# EEZ_DIB_DCP405_r2B11.net
KiCad netlist of a schematic drawn in EAGLE
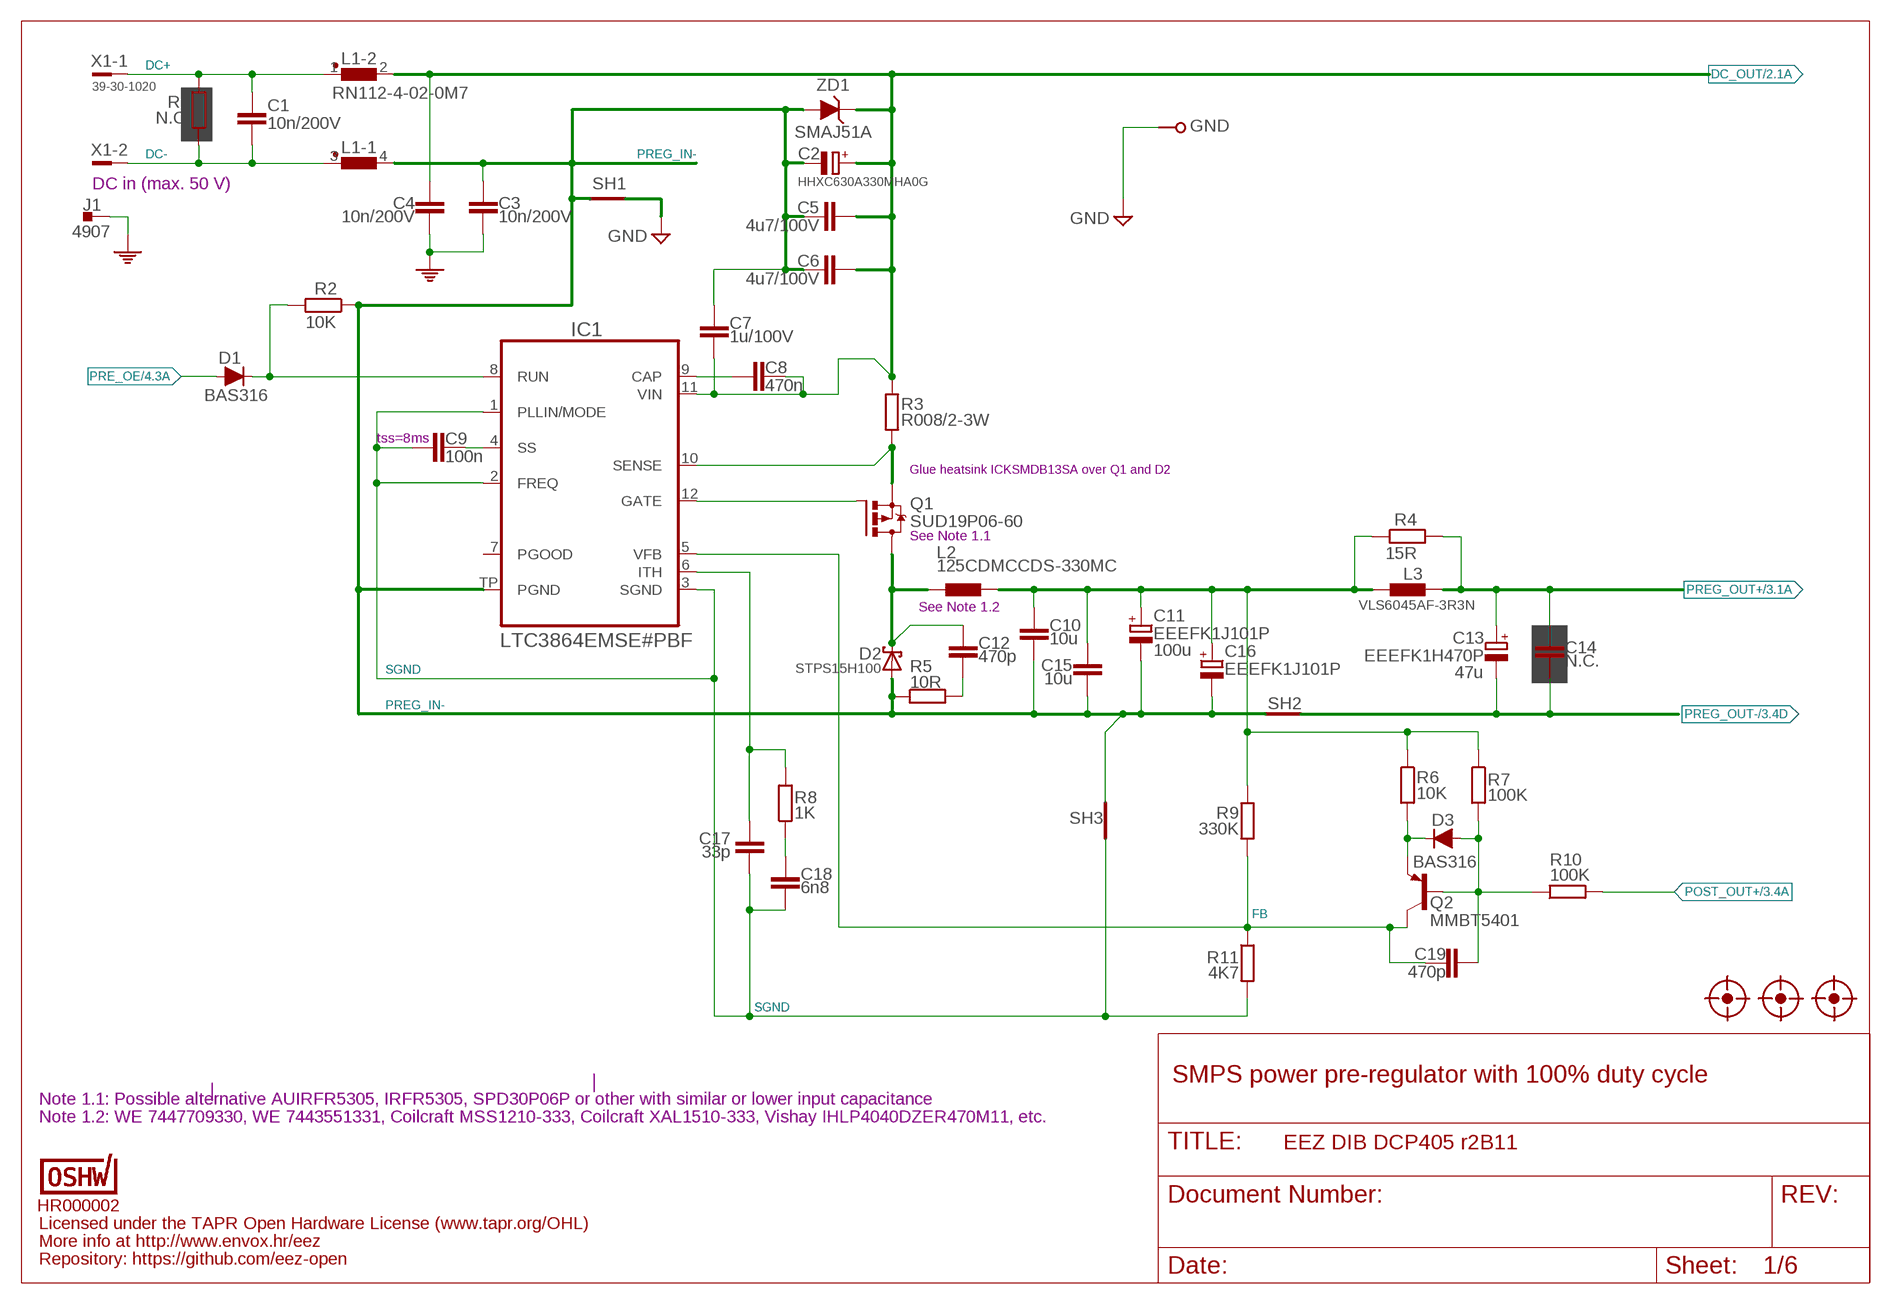
[diagram p0: schematic, sheet 1]
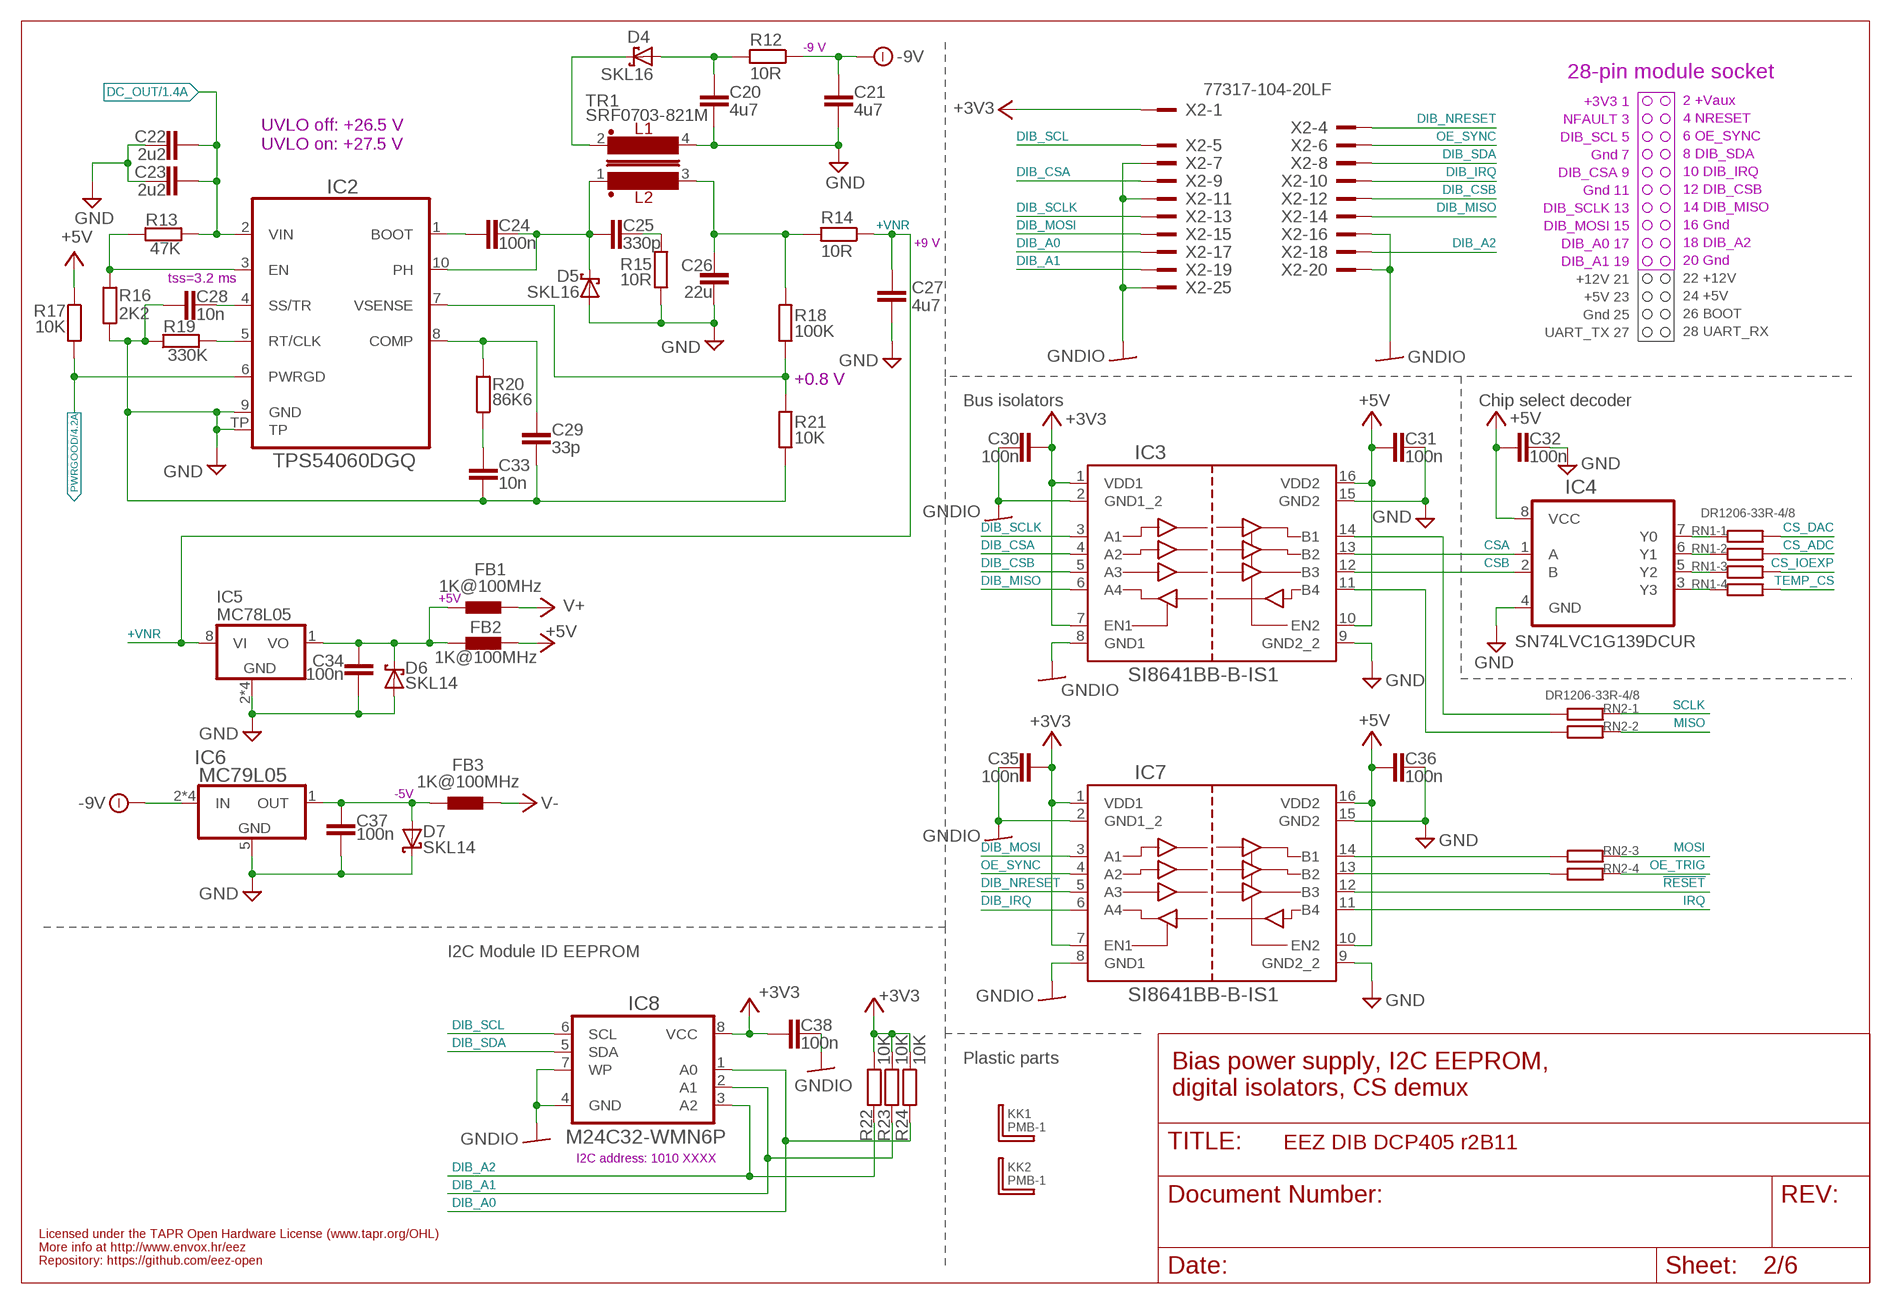
[diagram p1: schematic, sheet 2]
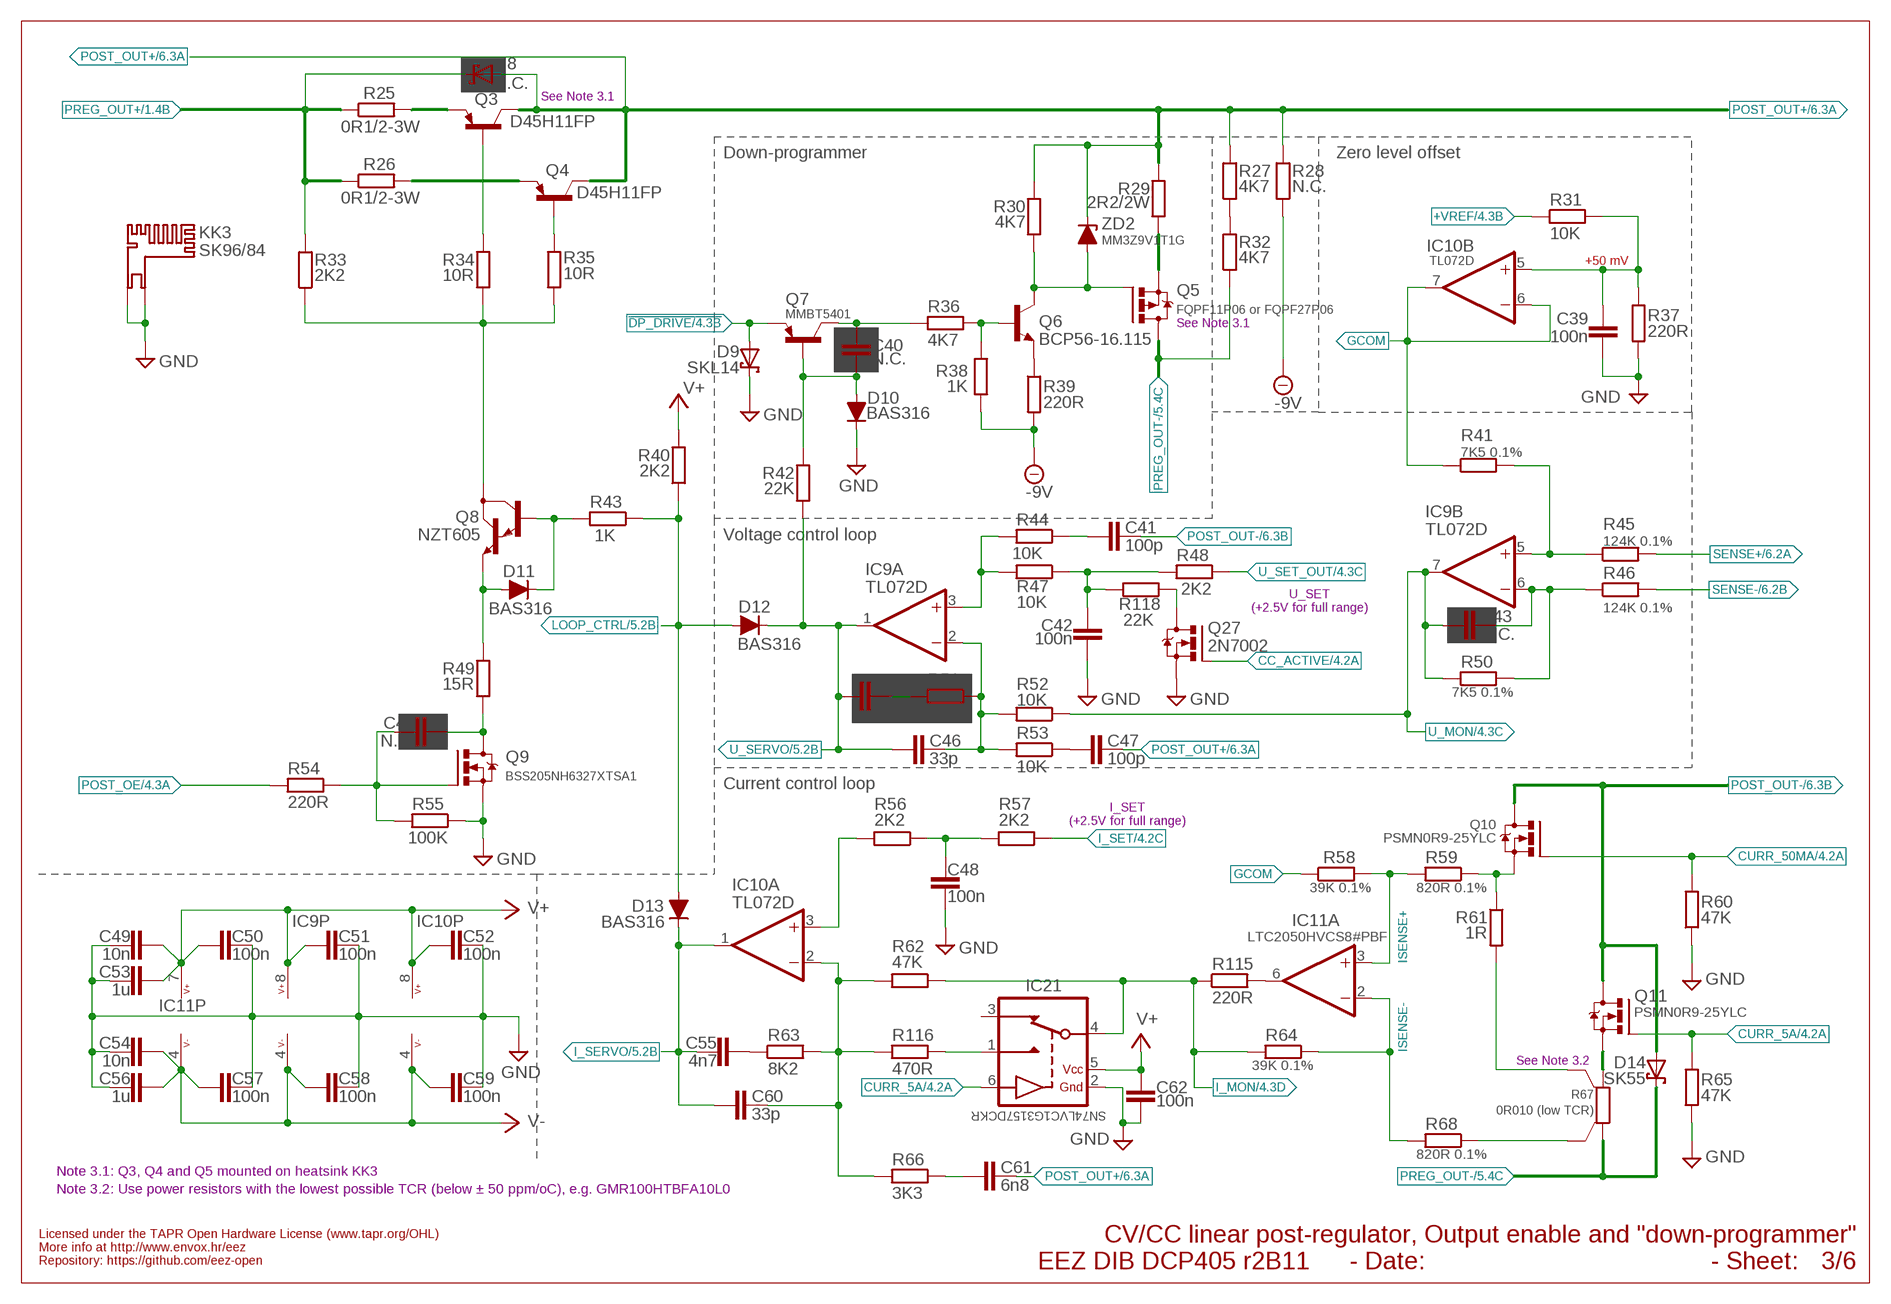
[diagram p2: schematic, sheet 3]
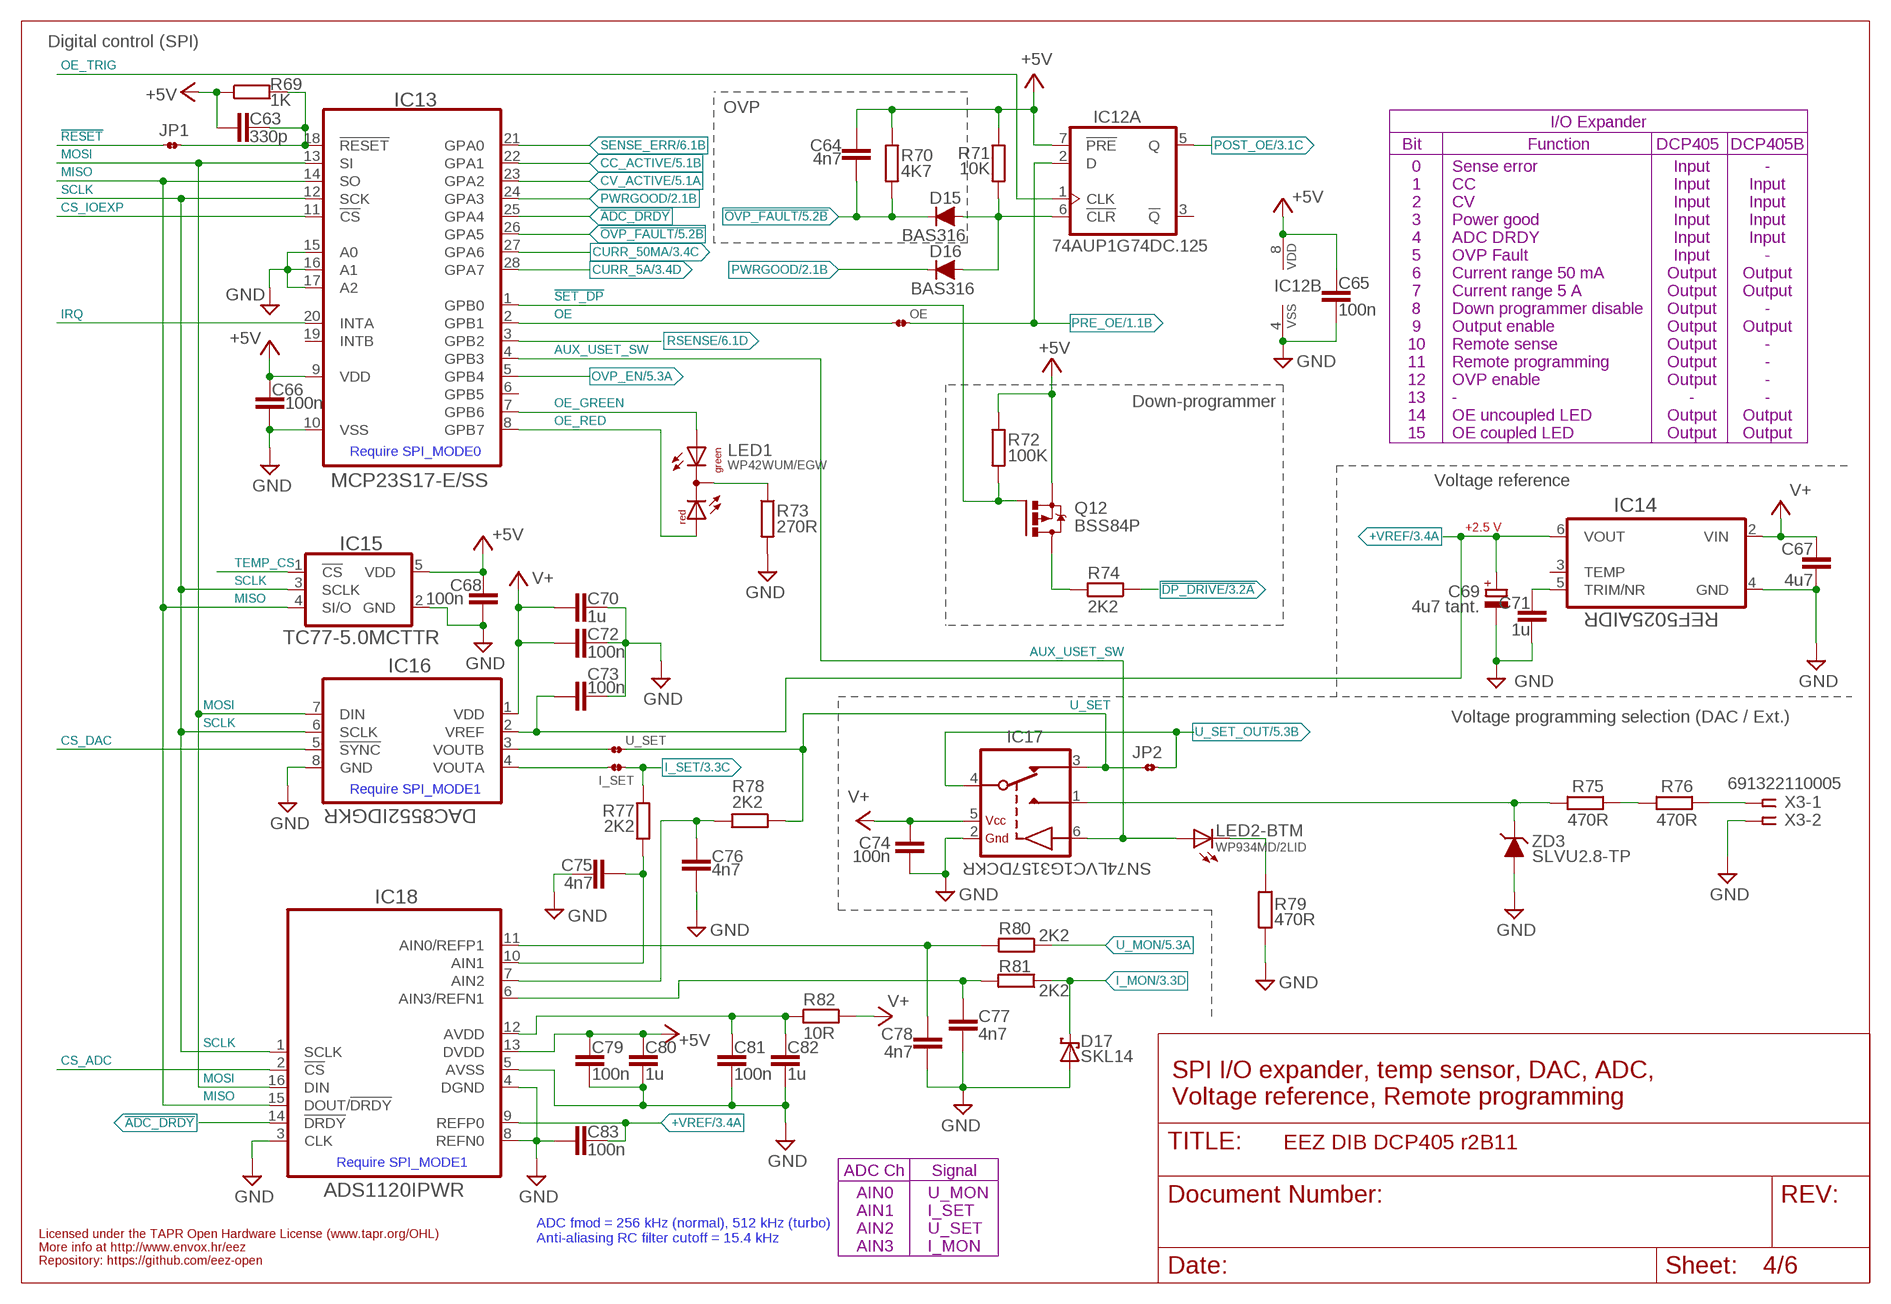
[diagram p3: schematic, sheet 4]
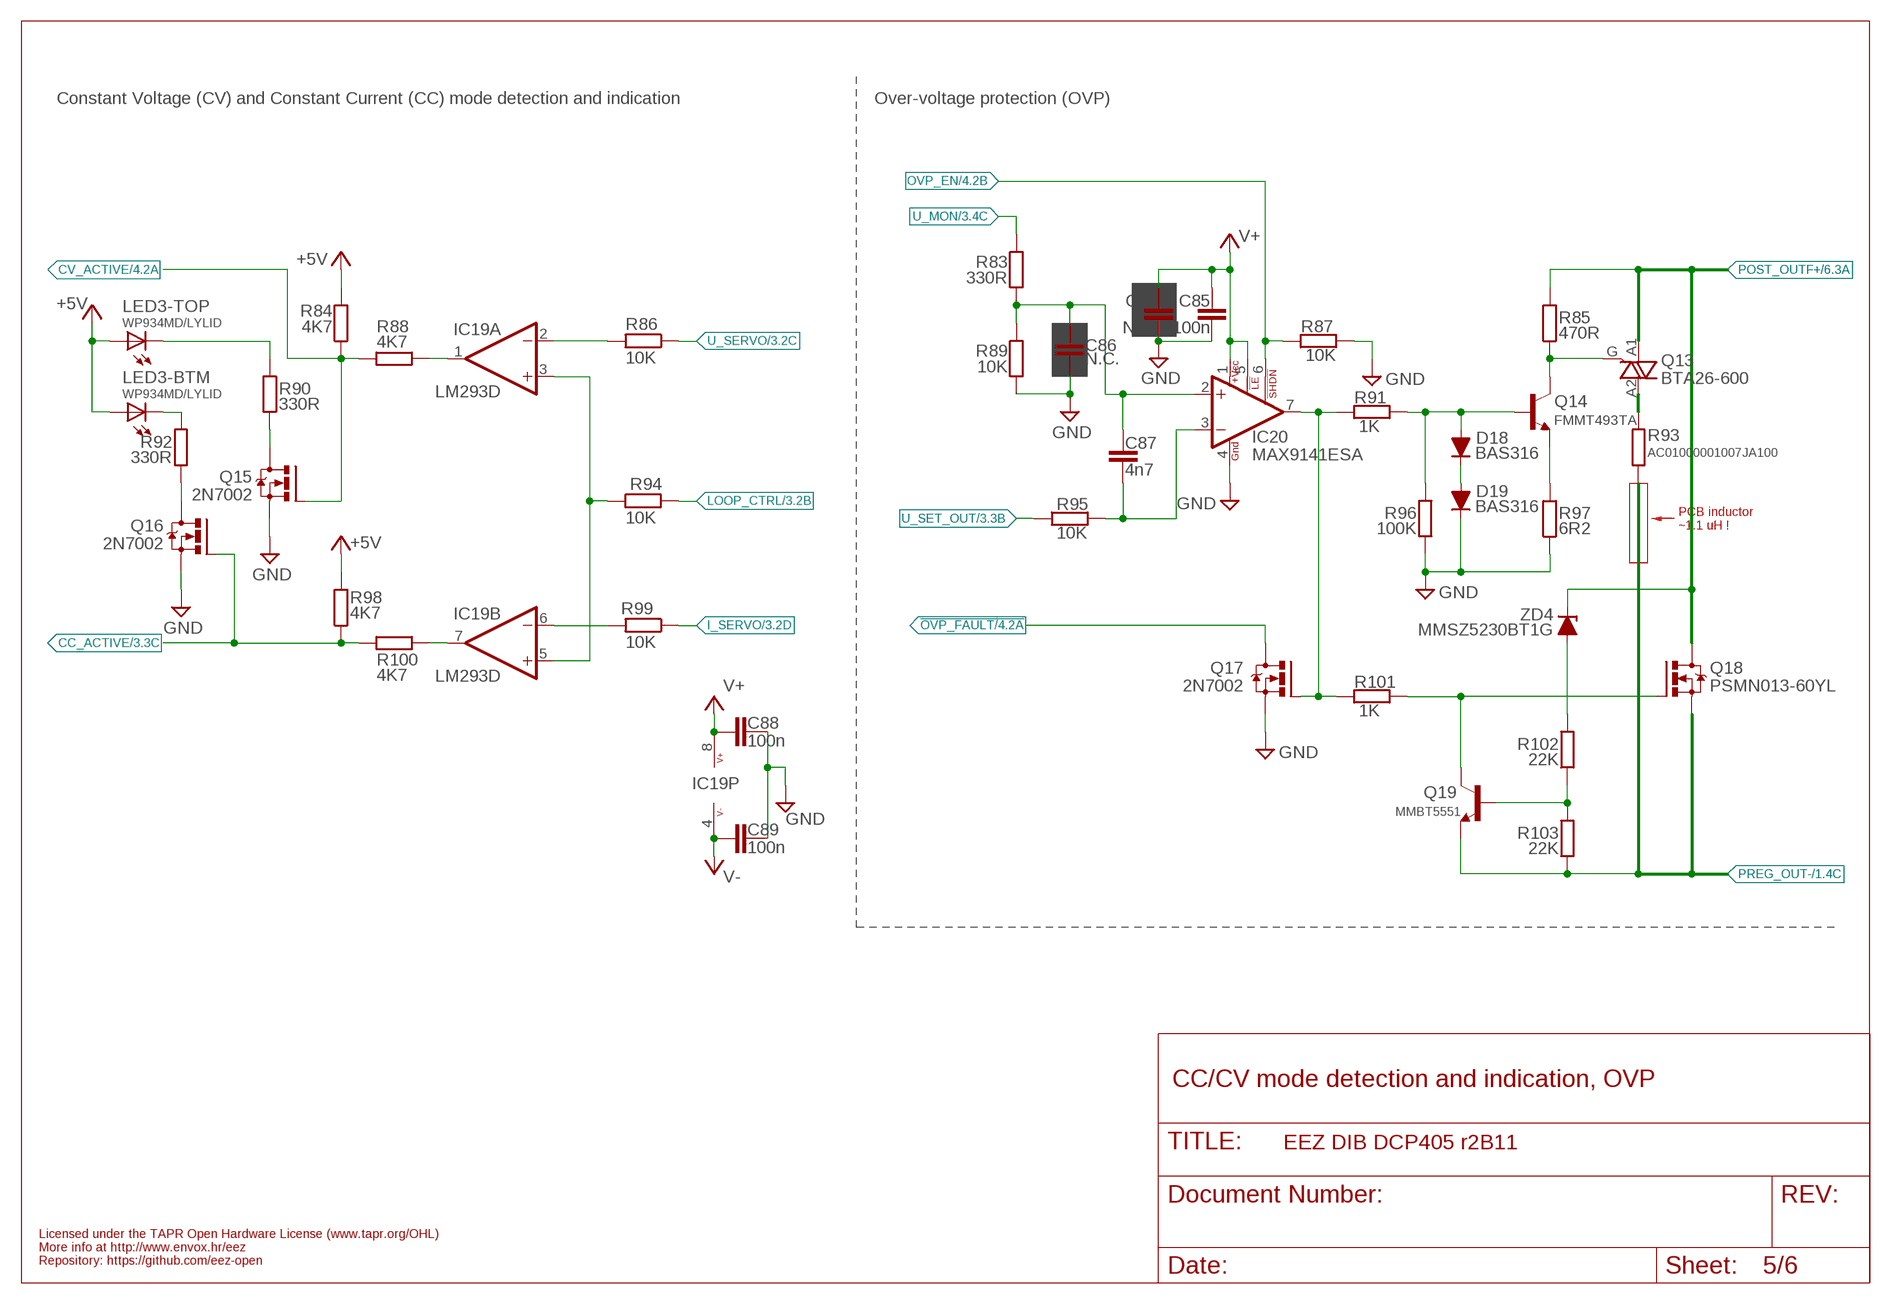
[diagram p4: schematic, sheet 5]
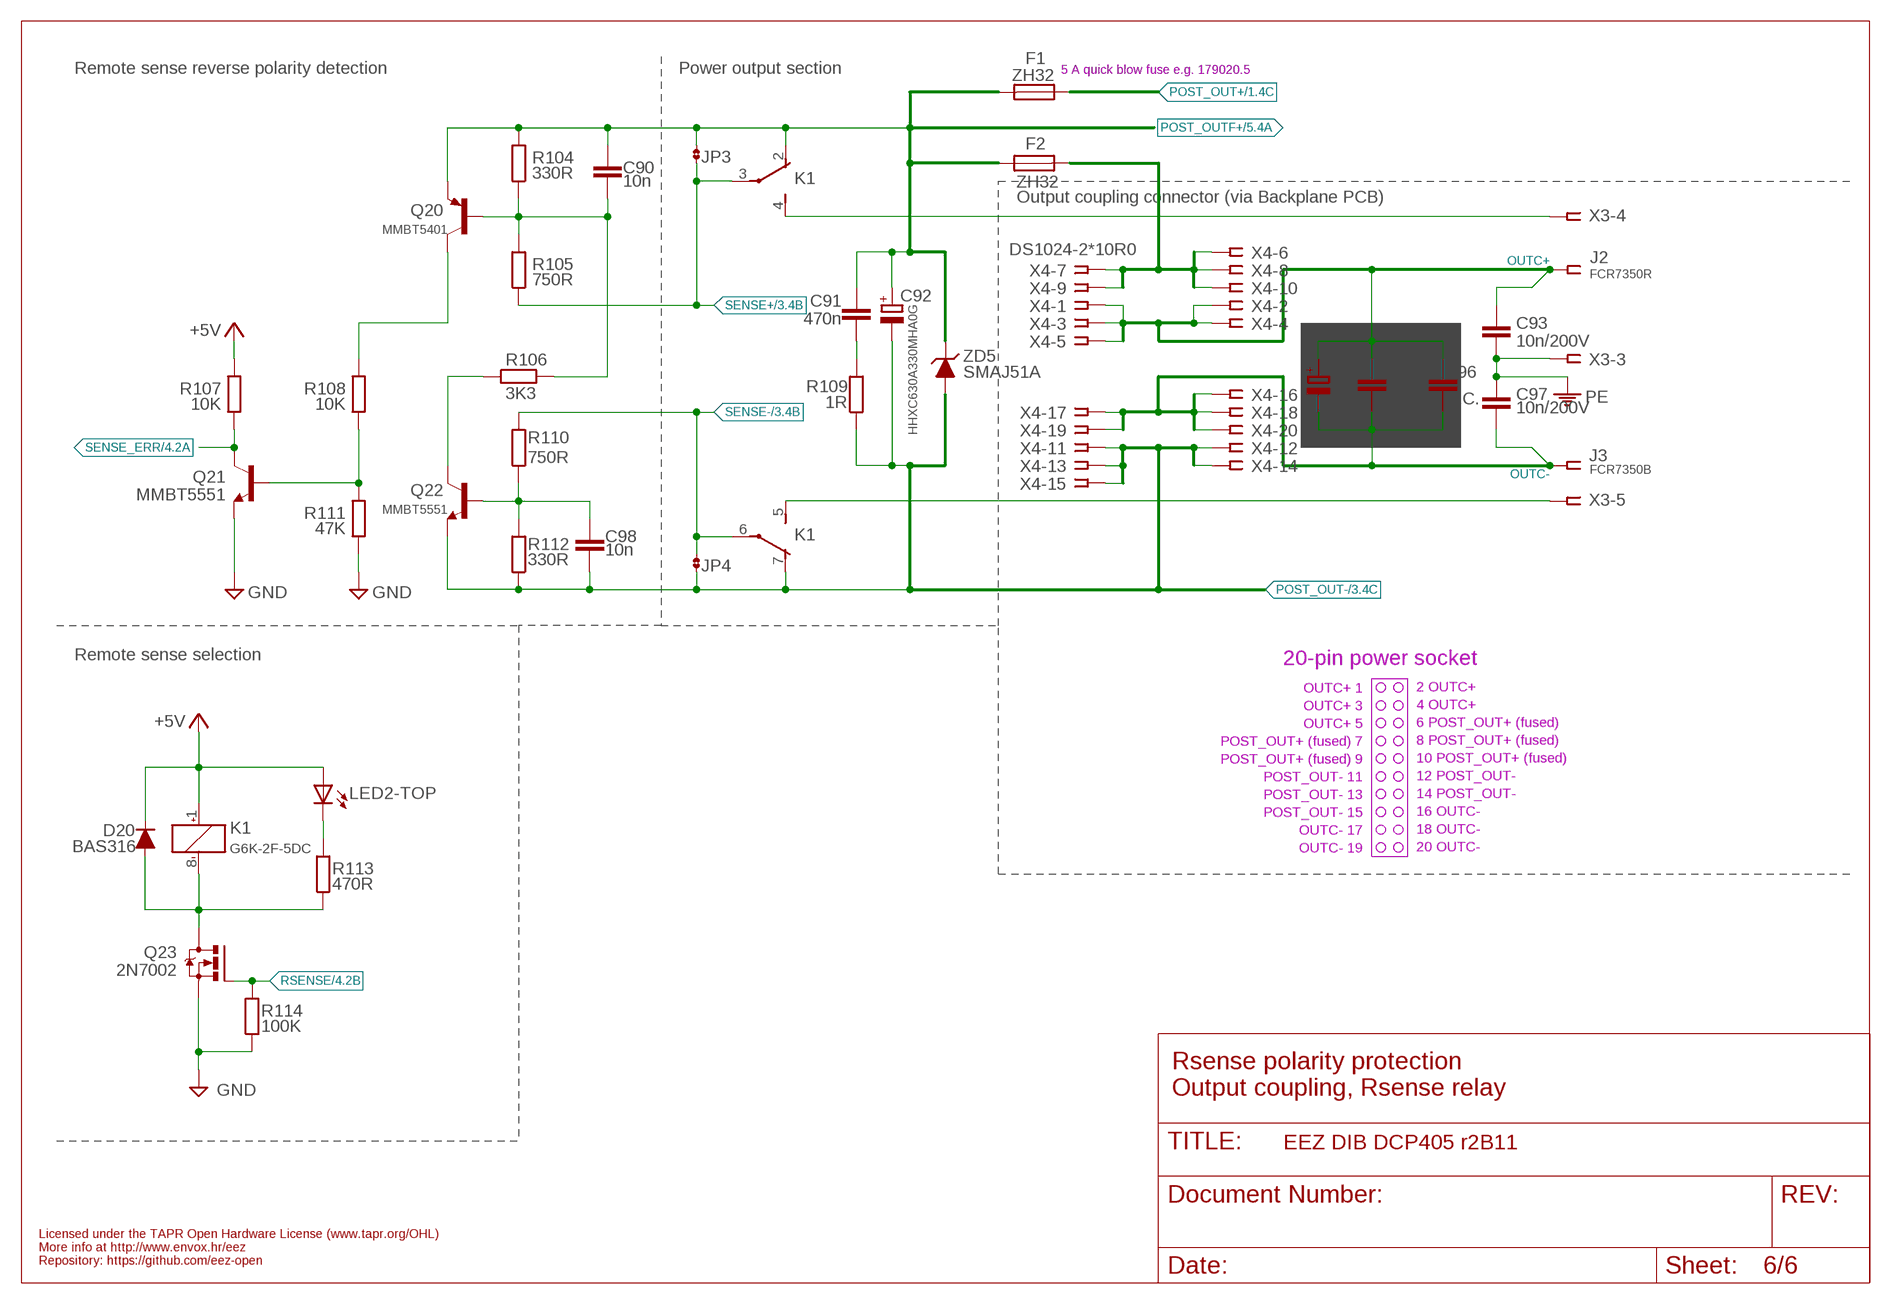
[diagram p5: schematic, sheet 6]

(export (version "E")
  (design (tool "Eeschema 10.0.6"))
  (components
    (comp (ref "C63")
      (value "330p")
      (footprint "eagle-import:C0805")
      (libsource (lib "eagle-import") (part "C-EUC0805"))
    )
    (comp (ref "C64")
      (value "4n7")
      (footprint "eagle-import:C0805")
      (libsource (lib "eagle-import") (part "C-EUC0805"))
    )
    (comp (ref "C65")
      (value "100n")
      (footprint "eagle-import:C0603")
      (libsource (lib "eagle-import") (part "C-EUC0603"))
    )
    (comp (ref "C66")
      (value "100n")
      (footprint "eagle-import:C0603")
      (libsource (lib "eagle-import") (part "C-EUC0603"))
    )
    (comp (ref "C67")
      (value "4u7")
      (footprint "eagle-import:C1206")
      (libsource (lib "eagle-import") (part "C-EUC1206"))
    )
    (comp (ref "C68")
      (value "100n")
      (footprint "eagle-import:C0603")
      (libsource (lib "eagle-import") (part "C-EUC0603"))
    )
    (comp (ref "C69")
      (value "4u7 tant.")
      (footprint "eagle-import:EC1206")
      (libsource (lib "eagle-import") (part "ECAP1206"))
    )
    (comp (ref "C70")
      (value "1u")
      (footprint "eagle-import:C0805")
      (libsource (lib "eagle-import") (part "C-EUC0805"))
    )
    (comp (ref "C71")
      (value "1u")
      (footprint "eagle-import:C0805")
      (libsource (lib "eagle-import") (part "C-EUC0805"))
    )
    (comp (ref "C72")
      (value "100n")
      (footprint "eagle-import:C0603")
      (libsource (lib "eagle-import") (part "C-EUC0603"))
    )
    (comp (ref "C73")
      (value "100n")
      (footprint "eagle-import:C0603")
      (libsource (lib "eagle-import") (part "C-EUC0603"))
    )
    (comp (ref "C74")
      (value "100n")
      (footprint "eagle-import:C0603")
      (libsource (lib "eagle-import") (part "C-EUC0603"))
    )
    (comp (ref "C75")
      (value "4n7")
      (footprint "eagle-import:C0805")
      (libsource (lib "eagle-import") (part "C-EUC0805"))
    )
    (comp (ref "C76")
      (value "4n7")
      (footprint "eagle-import:C0805")
      (libsource (lib "eagle-import") (part "C-EUC0805"))
    )
    (comp (ref "C77")
      (value "4n7")
      (footprint "eagle-import:C0805")
      (libsource (lib "eagle-import") (part "C-EUC0805"))
    )
    (comp (ref "C78")
      (value "4n7")
      (footprint "eagle-import:C0805")
      (libsource (lib "eagle-import") (part "C-EUC0805"))
    )
    (comp (ref "C79")
      (value "100n")
      (footprint "eagle-import:C0603")
      (libsource (lib "eagle-import") (part "C-EUC0603"))
    )
    (comp (ref "C80")
      (value "1u")
      (footprint "eagle-import:C0805")
      (libsource (lib "eagle-import") (part "C-EUC0805"))
    )
    (comp (ref "C81")
      (value "100n")
      (footprint "eagle-import:C0603")
      (libsource (lib "eagle-import") (part "C-EUC0603"))
    )
    (comp (ref "C82")
      (value "1u")
      (footprint "eagle-import:C0805")
      (libsource (lib "eagle-import") (part "C-EUC0805"))
    )
    (comp (ref "C83")
      (value "100n")
      (footprint "eagle-import:C0603")
      (libsource (lib "eagle-import") (part "C-EUC0603"))
    )
    (comp (ref "D15")
      (value "BAS316")
      (footprint "eagle-import:SOD323-R")
      (libsource (lib "eagle-import") (part "DIODESOD323R"))
    )
    (comp (ref "D16")
      (value "BAS316")
      (footprint "eagle-import:SOD323-R")
      (libsource (lib "eagle-import") (part "DIODESOD323R"))
    )
    (comp (ref "D17")
      (value "SKL14")
      (footprint "eagle-import:SOD123")
      (libsource (lib "eagle-import") (part "SCHOTTKYSOD123"))
    )
    (comp (ref "IC12")
      (value "74AUP1G74DC.125")
      (footprint "eagle-import:DCU8")
      (libsource (lib "eagle-import") (part "SN74LVC1G74DCTR-VSSOP"))
    )
    (comp (ref "IC13")
      (value "MCP23S17-E/SS")
      (footprint "eagle-import:SOP65P780X200-28N")
      (libsource (lib "eagle-import") (part "MCP23S17-E/SSSSOP"))
    )
    (comp (ref "IC14")
      (value "REF5025AIDR")
      (footprint "eagle-import:SOIC127P600X175-8N")
      (libsource (lib "eagle-import") (part "REF50XX"))
    )
    (comp (ref "IC15")
      (value "TC77-5.0MCTTR")
      (footprint "eagle-import:SOT23-5")
      (libsource (lib "eagle-import") (part "TC77"))
    )
    (comp (ref "IC16")
      (value "DAC8552IDGKR")
      (footprint "eagle-import:DGK8-M")
      (libsource (lib "eagle-import") (part "DAC8552_DGK_8M"))
    )
    (comp (ref "IC17")
      (value "SN74LVC1G3157DCKR")
      (footprint "eagle-import:SOT65P210X110-6N")
      (libsource (lib "eagle-import") (part "SN74LVC1G3157-DCK"))
    )
    (comp (ref "IC18")
      (value "ADS1120IPWR")
      (footprint "eagle-import:PW(R-PDSO-G16)")
      (libsource (lib "eagle-import") (part "ADS1120TSSOP-16"))
    )
    (comp (ref "I_SET")
      (value "JP2-NOCUT")
      (footprint "eagle-import:JP2-NOCUT")
      (libsource (lib "eagle-import") (part "JP2-NOCUT"))
    )
    (comp (ref "JP1")
      (value "JP2-NOCUT")
      (footprint "eagle-import:JP2-NOCUT")
      (libsource (lib "eagle-import") (part "JP2-NOCUT"))
    )
    (comp (ref "JP2")
      (value "JP2-CUT-0805")
      (footprint "eagle-import:R_0805")
      (libsource (lib "eagle-import") (part "JP2-CUT-0805"))
    )
    (comp (ref "LED1")
      (value "WP42WUM/EGW")
      (footprint "eagle-import:L-42WUM-1EGWT")
      (libsource (lib "eagle-import") (part "LED_L-42WUM/1EGWT"))
    )
    (comp (ref "LED2")
      (value "WP934MD/2LID")
      (footprint "eagle-import:WP934MD")
      (libsource (lib "eagle-import") (part "WP934MD/2LID"))
    )
    (comp (ref "OE")
      (value "JP2-NOCUT")
      (footprint "eagle-import:JP2-NOCUT")
      (libsource (lib "eagle-import") (part "JP2-NOCUT"))
    )
    (comp (ref "Q12")
      (value "BSS84P")
      (footprint "eagle-import:SOT95P237X112-3N")
      (fields (field (name "MPN") "IRLML2246TRPBF"))
      (libsource (lib "eagle-import") (part "IRLML2246TRPBF"))
    )
    (comp (ref "R69")
      (value "1K")
      (footprint "eagle-import:R0805")
      (libsource (lib "eagle-import") (part "R-EU_R0805"))
    )
    (comp (ref "R70")
      (value "4K7")
      (footprint "eagle-import:R0805")
      (libsource (lib "eagle-import") (part "R-EU_R0805"))
    )
    (comp (ref "R71")
      (value "10K")
      (footprint "eagle-import:R0805")
      (libsource (lib "eagle-import") (part "R-EU_R0805"))
    )
    (comp (ref "R72")
      (value "100K")
      (footprint "eagle-import:R0805")
      (libsource (lib "eagle-import") (part "R-EU_R0805"))
    )
    (comp (ref "R73")
      (value "270R")
      (footprint "eagle-import:R0805")
      (libsource (lib "eagle-import") (part "R-EU_R0805"))
    )
    (comp (ref "R74")
      (value "2K2")
      (footprint "eagle-import:R0805")
      (libsource (lib "eagle-import") (part "R-EU_R0805"))
    )
    (comp (ref "R75")
      (value "470R")
      (footprint "eagle-import:R0805")
      (libsource (lib "eagle-import") (part "R-EU_R0805"))
    )
    (comp (ref "R76")
      (value "470R")
      (footprint "eagle-import:R0805")
      (libsource (lib "eagle-import") (part "R-EU_R0805"))
    )
    (comp (ref "R77")
      (value "2K2")
      (footprint "eagle-import:R0805")
      (libsource (lib "eagle-import") (part "R-EU_R0805"))
    )
    (comp (ref "R78")
      (value "2K2")
      (footprint "eagle-import:R0805")
      (libsource (lib "eagle-import") (part "R-EU_R0805"))
    )
    (comp (ref "R79")
      (value "470R")
      (footprint "eagle-import:R0805")
      (libsource (lib "eagle-import") (part "R-EU_R0805"))
    )
    (comp (ref "R80")
      (value "2K2")
      (footprint "eagle-import:R0805")
      (libsource (lib "eagle-import") (part "R-EU_R0805"))
    )
    (comp (ref "R81")
      (value "2K2")
      (footprint "eagle-import:R0805")
      (libsource (lib "eagle-import") (part "R-EU_R0805"))
    )
    (comp (ref "R82")
      (value "10R")
      (footprint "eagle-import:R1206")
      (libsource (lib "eagle-import") (part "R-EU_R1206"))
    )
    (comp (ref "U_SET")
      (value "JP2-NOCUT")
      (footprint "eagle-import:JP2-NOCUT")
      (libsource (lib "eagle-import") (part "JP2-NOCUT"))
    )
    (comp (ref "X3")
      (value "691322110005")
      (footprint "eagle-import:MC1,5_5-G-3,5")
      (libsource (lib "eagle-import") (part "MC1,5/5-G-3,5"))
    )
    (comp (ref "ZD3")
      (value "SLVU2.8-TP")
      (footprint "eagle-import:SOT23")
      (libsource (lib "eagle-import") (part "SLVU2.8"))
    )
    (comp (ref "C20")
      (value "4u7")
      (footprint "eagle-import:C1206")
      (libsource (lib "eagle-import") (part "C-EUC1206"))
    )
    (comp (ref "C21")
      (value "4u7")
      (footprint "eagle-import:C1206")
      (libsource (lib "eagle-import") (part "C-EUC1206"))
    )
    (comp (ref "C22")
      (value "2u2")
      (footprint "eagle-import:C1206")
      (libsource (lib "eagle-import") (part "C-EUC1206"))
    )
    (comp (ref "C23")
      (value "2u2")
      (footprint "eagle-import:C1206")
      (libsource (lib "eagle-import") (part "C-EUC1206"))
    )
    (comp (ref "C24")
      (value "100n")
      (footprint "eagle-import:C0603")
      (libsource (lib "eagle-import") (part "C-EUC0603"))
    )
    (comp (ref "C25")
      (value "330p")
      (footprint "eagle-import:C0805")
      (libsource (lib "eagle-import") (part "C-EUC0805"))
    )
    (comp (ref "C26")
      (value "22u")
      (footprint "eagle-import:C1210")
      (libsource (lib "eagle-import") (part "C-EUC1210"))
    )
    (comp (ref "C27")
      (value "4u7")
      (footprint "eagle-import:C1206")
      (libsource (lib "eagle-import") (part "C-EUC1206"))
    )
    (comp (ref "C28")
      (value "10n")
      (footprint "eagle-import:C0805")
      (libsource (lib "eagle-import") (part "C-EUC0805"))
    )
    (comp (ref "C29")
      (value "33p")
      (footprint "eagle-import:C0805")
      (libsource (lib "eagle-import") (part "C-EUC0805"))
    )
    (comp (ref "C30")
      (value "100n")
      (footprint "eagle-import:C0603")
      (libsource (lib "eagle-import") (part "C-EUC0603"))
    )
    (comp (ref "C31")
      (value "100n")
      (footprint "eagle-import:C0603")
      (libsource (lib "eagle-import") (part "C-EUC0603"))
    )
    (comp (ref "C32")
      (value "100n")
      (footprint "eagle-import:C0603")
      (libsource (lib "eagle-import") (part "C-EUC0603"))
    )
    (comp (ref "C33")
      (value "10n")
      (footprint "eagle-import:C0805")
      (libsource (lib "eagle-import") (part "C-EUC0805"))
    )
    (comp (ref "C34")
      (value "100n")
      (footprint "eagle-import:C0603")
      (libsource (lib "eagle-import") (part "C-EUC0603"))
    )
    (comp (ref "C35")
      (value "100n")
      (footprint "eagle-import:C0603")
      (libsource (lib "eagle-import") (part "C-EUC0603"))
    )
    (comp (ref "C36")
      (value "100n")
      (footprint "eagle-import:C0603")
      (libsource (lib "eagle-import") (part "C-EUC0603"))
    )
    (comp (ref "C37")
      (value "100n")
      (footprint "eagle-import:C0603")
      (libsource (lib "eagle-import") (part "C-EUC0603"))
    )
    (comp (ref "C38")
      (value "100n")
      (footprint "eagle-import:C0603")
      (libsource (lib "eagle-import") (part "C-EUC0603"))
    )
    (comp (ref "D4")
      (value "SKL16")
      (footprint "eagle-import:SOD123")
      (libsource (lib "eagle-import") (part "SCHOTTKYSOD123"))
    )
    (comp (ref "D5")
      (value "SKL16")
      (footprint "eagle-import:SOD123")
      (libsource (lib "eagle-import") (part "SCHOTTKYSOD123"))
    )
    (comp (ref "D6")
      (value "SKL14")
      (footprint "eagle-import:SOD123")
      (libsource (lib "eagle-import") (part "SCHOTTKYSOD123"))
    )
    (comp (ref "D7")
      (value "SKL14")
      (footprint "eagle-import:SOD123")
      (libsource (lib "eagle-import") (part "SCHOTTKYSOD123"))
    )
    (comp (ref "FB1")
      (value "1K@100MHz")
      (footprint "eagle-import:BEAD0603")
      (libsource (lib "eagle-import") (part "FERRITE_BEAD0603"))
    )
    (comp (ref "FB2")
      (value "1K@100MHz")
      (footprint "eagle-import:BEAD0603")
      (libsource (lib "eagle-import") (part "FERRITE_BEAD0603"))
    )
    (comp (ref "FB3")
      (value "1K@100MHz")
      (footprint "eagle-import:BEAD0603")
      (libsource (lib "eagle-import") (part "FERRITE_BEAD0603"))
    )
    (comp (ref "IC2")
      (value "TPS54060DGQ")
      (footprint "eagle-import:SOP50P490X110-11N")
      (fields (field (name "MPN") "TPS54060ADGQ"))
      (libsource (lib "eagle-import") (part "TPS54060DGQ"))
    )
    (comp (ref "IC3")
      (value "SI8641BB-B-IS1")
      (footprint "eagle-import:SOIC-16")
      (libsource (lib "eagle-import") (part "SI8641NSOIC-16"))
    )
    (comp (ref "IC4")
      (value "SN74LVC1G139DCUR")
      (footprint "eagle-import:DCU8")
      (libsource (lib "eagle-import") (part "SN74LVC1G139-VSSOP"))
    )
    (comp (ref "IC5")
      (value "MC78L05")
      (footprint "eagle-import:SOIC127P600X173-8N")
      (libsource (lib "eagle-import") (part "MC78LXXSOIC8"))
    )
    (comp (ref "IC6")
      (value "MC79L05")
      (footprint "eagle-import:SOIC127P600X173-8N")
      (libsource (lib "eagle-import") (part "MC79LXXSOIC"))
    )
    (comp (ref "IC7")
      (value "SI8641BB-B-IS1")
      (footprint "eagle-import:SOIC-16")
      (libsource (lib "eagle-import") (part "SI8641NSOIC-16"))
    )
    (comp (ref "IC8")
      (value "M24C32-WMN6P")
      (footprint "eagle-import:SOIC127P600X173-8N")
      (libsource (lib "eagle-import") (part "AT24CXXSOIC8"))
    )
    (comp (ref "KK1")
      (value "PMB-1")
      (footprint "eagle-import:PCB-MB")
      (libsource (lib "eagle-import") (part "PCB-MB"))
    )
    (comp (ref "KK2")
      (value "PMB-1")
      (footprint "eagle-import:PCB-MB")
      (libsource (lib "eagle-import") (part "PCB-MB"))
    )
    (comp (ref "R12")
      (value "10R")
      (footprint "eagle-import:R1206")
      (libsource (lib "eagle-import") (part "R-EU_R1206"))
    )
    (comp (ref "R13")
      (value "47K")
      (footprint "eagle-import:R0805")
      (libsource (lib "eagle-import") (part "R-EU_R0805"))
    )
    (comp (ref "R14")
      (value "10R")
      (footprint "eagle-import:R1206")
      (libsource (lib "eagle-import") (part "R-EU_R1206"))
    )
    (comp (ref "R15")
      (value "10R")
      (footprint "eagle-import:R1206")
      (libsource (lib "eagle-import") (part "R-EU_R1206"))
    )
    (comp (ref "R16")
      (value "2K2")
      (footprint "eagle-import:R0805")
      (libsource (lib "eagle-import") (part "R-EU_R0805"))
    )
    (comp (ref "R17")
      (value "10K")
      (footprint "eagle-import:R0805")
      (libsource (lib "eagle-import") (part "R-EU_R0805"))
    )
    (comp (ref "R18")
      (value "100K")
      (footprint "eagle-import:R0805")
      (libsource (lib "eagle-import") (part "R-EU_R0805"))
    )
    (comp (ref "R19")
      (value "330K")
      (footprint "eagle-import:R0805")
      (libsource (lib "eagle-import") (part "R-EU_R0805"))
    )
    (comp (ref "R20")
      (value "86K6")
      (footprint "eagle-import:R0805")
      (libsource (lib "eagle-import") (part "R-EU_R0805"))
    )
    (comp (ref "R21")
      (value "10K")
      (footprint "eagle-import:R0805")
      (libsource (lib "eagle-import") (part "R-EU_R0805"))
    )
    (comp (ref "R22")
      (value "10K")
      (footprint "eagle-import:R0805")
      (libsource (lib "eagle-import") (part "R-EU_R0805"))
    )
    (comp (ref "R23")
      (value "10K")
      (footprint "eagle-import:R0805")
      (libsource (lib "eagle-import") (part "R-EU_R0805"))
    )
    (comp (ref "R24")
      (value "10K")
      (footprint "eagle-import:R0805")
      (libsource (lib "eagle-import") (part "R-EU_R0805"))
    )
    (comp (ref "RN1")
      (value "DR1206-33R-4/8")
      (footprint "eagle-import:CAY16")
      (libsource (lib "eagle-import") (part "R_ARRAY4"))
    )
    (comp (ref "RN2")
      (value "DR1206-33R-4/8")
      (footprint "eagle-import:CAY16")
      (libsource (lib "eagle-import") (part "R_ARRAY4"))
    )
    (comp (ref "TR1")
      (value "SRF0703-821M")
      (footprint "eagle-import:SRF0703")
      (libsource (lib "eagle-import") (part "BOURNS_SRF0703INV"))
    )
    (comp (ref "X2")
      (value "77317-104-20LF")
      (footprint "eagle-import:77317-104-28LF")
      (libsource (lib "eagle-import") (part "77317-104-28LF"))
    )
    (comp (ref "C84")
      (value "N.C.")
      (footprint "eagle-import:C0805")
      (libsource (lib "eagle-import") (part "C-EUC0805"))
    )
    (comp (ref "C85")
      (value "100n")
      (footprint "eagle-import:C0603")
      (libsource (lib "eagle-import") (part "C-EUC0603"))
    )
    (comp (ref "C86")
      (value "N.C.")
      (footprint "eagle-import:C0805")
      (libsource (lib "eagle-import") (part "C-EUC0805"))
    )
    (comp (ref "C87")
      (value "4n7")
      (footprint "eagle-import:C0805")
      (libsource (lib "eagle-import") (part "C-EUC0805"))
    )
    (comp (ref "C88")
      (value "100n")
      (footprint "eagle-import:C0603")
      (libsource (lib "eagle-import") (part "C-EUC0603"))
    )
    (comp (ref "C89")
      (value "100n")
      (footprint "eagle-import:C0603")
      (libsource (lib "eagle-import") (part "C-EUC0603"))
    )
    (comp (ref "D18")
      (value "BAS316")
      (footprint "eagle-import:SOD323-R")
      (libsource (lib "eagle-import") (part "DIODESOD323R"))
    )
    (comp (ref "D19")
      (value "BAS316")
      (footprint "eagle-import:SOD323-R")
      (libsource (lib "eagle-import") (part "DIODESOD323R"))
    )
    (comp (ref "IC19")
      (value "LM293D")
      (footprint "eagle-import:SOIC127P600X173-8N")
      (libsource (lib "eagle-import") (part "LM293D"))
    )
    (comp (ref "IC20")
      (value "MAX9141ESA")
      (footprint "eagle-import:SOIC127P600X173-8N")
      (libsource (lib "eagle-import") (part "MAX9141ESA"))
    )
    (comp (ref "LED3")
      (value "WP934MD/LYLID")
      (footprint "eagle-import:WP934MD")
      (libsource (lib "eagle-import") (part "WP934MD/LYLID"))
    )
    (comp (ref "Q13")
      (value "BTA26-600")
      (footprint "eagle-import:TOP3_TRIAC_NOHOLE")
      (libsource (lib "eagle-import") (part "BTA41-2"))
    )
    (comp (ref "Q14")
      (value "FMMT493TA")
      (footprint "eagle-import:SOT23-BEC")
      (libsource (lib "eagle-import") (part "-NPN-SOT23-BECMMBT5551LT1"))
    )
    (comp (ref "Q15")
      (value "2N7002")
      (footprint "eagle-import:SOT103P240X110-3N")
      (fields (field (name "MPN") "2N7002-7-F"))
      (libsource (lib "eagle-import") (part "2N7002"))
    )
    (comp (ref "Q16")
      (value "2N7002")
      (footprint "eagle-import:SOT103P240X110-3N")
      (fields (field (name "MPN") "2N7002-7-F"))
      (libsource (lib "eagle-import") (part "2N7002"))
    )
    (comp (ref "Q17")
      (value "2N7002")
      (footprint "eagle-import:SOT103P240X110-3N")
      (fields
        (field (name "MPN") "2N7002-7-F")
        (field (name "MPN_1") "2N7002-7-F")
        (field (name "OC_FARNELL") "1713823")
        (field (name "OC_NEWARK") "25R5679")
        (field (name "PACKAGE") "SOT-23-3")
        (field (name "SUPPLIER") "DIODES INC.")
      )
      (libsource (lib "eagle-import") (part "2N7002"))
    )
    (comp (ref "Q18")
      (value "PSMN013-60YL")
      (footprint "eagle-import:SOT669")
      (libsource (lib "eagle-import") (part "N-MOSFETLFPAK"))
    )
    (comp (ref "Q19")
      (value "MMBT5551")
      (footprint "eagle-import:SOT23-BEC")
      (libsource (lib "eagle-import") (part "-NPN-SOT23-BECMMBT5551LT1"))
    )
    (comp (ref "R83")
      (value "330R")
      (footprint "eagle-import:R0805")
      (libsource (lib "eagle-import") (part "R-EU_R0805"))
    )
    (comp (ref "R84")
      (value "4K7")
      (footprint "eagle-import:R0805")
      (libsource (lib "eagle-import") (part "R-EU_R0805"))
    )
    (comp (ref "R85")
      (value "470R")
      (footprint "eagle-import:R0805")
      (libsource (lib "eagle-import") (part "R-EU_R0805"))
    )
    (comp (ref "R86")
      (value "10K")
      (footprint "eagle-import:R0805")
      (libsource (lib "eagle-import") (part "R-EU_R0805"))
    )
    (comp (ref "R87")
      (value "10K")
      (footprint "eagle-import:R0805")
      (libsource (lib "eagle-import") (part "R-EU_R0805"))
    )
    (comp (ref "R88")
      (value "4K7")
      (footprint "eagle-import:R0805")
      (libsource (lib "eagle-import") (part "R-EU_R0805"))
    )
    (comp (ref "R89")
      (value "10K")
      (footprint "eagle-import:R0805")
      (libsource (lib "eagle-import") (part "R-EU_R0805"))
    )
    (comp (ref "R90")
      (value "330R")
      (footprint "eagle-import:R0805")
      (libsource (lib "eagle-import") (part "R-EU_R0805"))
    )
    (comp (ref "R91")
      (value "1K")
      (footprint "eagle-import:R0805")
      (libsource (lib "eagle-import") (part "R-EU_R0805"))
    )
    (comp (ref "R92")
      (value "330R")
      (footprint "eagle-import:R0805")
      (libsource (lib "eagle-import") (part "R-EU_R0805"))
    )
    (comp (ref "R93")
      (value "AC01000001007JA100")
      (footprint "eagle-import:0411_15")
      (libsource (lib "eagle-import") (part "R-EU_0411/15"))
    )
    (comp (ref "R94")
      (value "10K")
      (footprint "eagle-import:R0805")
      (libsource (lib "eagle-import") (part "R-EU_R0805"))
    )
    (comp (ref "R95")
      (value "10K")
      (footprint "eagle-import:R0805")
      (libsource (lib "eagle-import") (part "R-EU_R0805"))
    )
    (comp (ref "R96")
      (value "100K")
      (footprint "eagle-import:R0805")
      (libsource (lib "eagle-import") (part "R-EU_R0805"))
    )
    (comp (ref "R97")
      (value "6R2")
      (footprint "eagle-import:R0805")
      (libsource (lib "eagle-import") (part "R-EU_R0805"))
    )
    (comp (ref "R98")
      (value "4K7")
      (footprint "eagle-import:R0805")
      (libsource (lib "eagle-import") (part "R-EU_R0805"))
    )
    (comp (ref "R99")
      (value "10K")
      (footprint "eagle-import:R0805")
      (libsource (lib "eagle-import") (part "R-EU_R0805"))
    )
    (comp (ref "R100")
      (value "4K7")
      (footprint "eagle-import:R0805")
      (libsource (lib "eagle-import") (part "R-EU_R0805"))
    )
    (comp (ref "R101")
      (value "1K")
      (footprint "eagle-import:R0805")
      (libsource (lib "eagle-import") (part "R-EU_R0805"))
    )
    (comp (ref "R102")
      (value "22K")
      (footprint "eagle-import:R0805")
      (libsource (lib "eagle-import") (part "R-EU_R0805"))
    )
    (comp (ref "R103")
      (value "22K")
      (footprint "eagle-import:R0805")
      (libsource (lib "eagle-import") (part "R-EU_R0805"))
    )
    (comp (ref "ZD4")
      (value "MMSZ5230BT1G")
      (footprint "eagle-import:SOD123")
      (libsource (lib "eagle-import") (part "ZENER-DIODESOD123"))
    )
    (comp (ref "C39")
      (value "100n")
      (footprint "eagle-import:C0603")
      (libsource (lib "eagle-import") (part "C-EUC0603"))
    )
    (comp (ref "C40")
      (value "N.C.")
      (footprint "eagle-import:C0805")
      (libsource (lib "eagle-import") (part "C-EUC0805"))
    )
    (comp (ref "C41")
      (value "100p")
      (footprint "eagle-import:C0805")
      (libsource (lib "eagle-import") (part "C-EUC0805"))
    )
    (comp (ref "C42")
      (value "100n")
      (footprint "eagle-import:C0603")
      (libsource (lib "eagle-import") (part "C-EUC0603"))
    )
    (comp (ref "C43")
      (value "N.C.")
      (footprint "eagle-import:C0805")
      (libsource (lib "eagle-import") (part "C-EUC0805"))
    )
    (comp (ref "C44")
      (value "N.C.")
      (footprint "eagle-import:C0805")
      (libsource (lib "eagle-import") (part "C-EUC0805"))
    )
    (comp (ref "C45")
      (value "N.C.")
      (footprint "eagle-import:C0805")
      (libsource (lib "eagle-import") (part "C-EUC0805"))
    )
    (comp (ref "C46")
      (value "33p")
      (footprint "eagle-import:C0805")
      (libsource (lib "eagle-import") (part "C-EUC0805"))
    )
    (comp (ref "C47")
      (value "100p")
      (footprint "eagle-import:C0805")
      (libsource (lib "eagle-import") (part "C-EUC0805"))
    )
    (comp (ref "C48")
      (value "100n")
      (footprint "eagle-import:C0603")
      (libsource (lib "eagle-import") (part "C-EUC0603"))
    )
    (comp (ref "C49")
      (value "10n")
      (footprint "eagle-import:C0805")
      (libsource (lib "eagle-import") (part "C-EUC0805"))
    )
    (comp (ref "C50")
      (value "100n")
      (footprint "eagle-import:C0603")
      (libsource (lib "eagle-import") (part "C-EUC0603"))
    )
    (comp (ref "C51")
      (value "100n")
      (footprint "eagle-import:C0603")
      (libsource (lib "eagle-import") (part "C-EUC0603"))
    )
    (comp (ref "C52")
      (value "100n")
      (footprint "eagle-import:C0603")
      (libsource (lib "eagle-import") (part "C-EUC0603"))
    )
    (comp (ref "C53")
      (value "1u")
      (footprint "eagle-import:C0805")
      (libsource (lib "eagle-import") (part "C-EUC0805"))
    )
    (comp (ref "C54")
      (value "10n")
      (footprint "eagle-import:C0805")
      (libsource (lib "eagle-import") (part "C-EUC0805"))
    )
    (comp (ref "C55")
      (value "4n7")
      (footprint "eagle-import:C0805")
      (libsource (lib "eagle-import") (part "C-EUC0805"))
    )
    (comp (ref "C56")
      (value "1u")
      (footprint "eagle-import:C0805")
      (libsource (lib "eagle-import") (part "C-EUC0805"))
    )
    (comp (ref "C57")
      (value "100n")
      (footprint "eagle-import:C0603")
      (libsource (lib "eagle-import") (part "C-EUC0603"))
    )
    (comp (ref "C58")
      (value "100n")
      (footprint "eagle-import:C0603")
      (libsource (lib "eagle-import") (part "C-EUC0603"))
    )
    (comp (ref "C59")
      (value "100n")
      (footprint "eagle-import:C0603")
      (libsource (lib "eagle-import") (part "C-EUC0603"))
    )
    (comp (ref "C60")
      (value "33p")
      (footprint "eagle-import:C0805")
      (libsource (lib "eagle-import") (part "C-EUC0805"))
    )
    (comp (ref "C61")
      (value "6n8")
      (footprint "eagle-import:C0805")
      (libsource (lib "eagle-import") (part "C-EUC0805"))
    )
    (comp (ref "C62")
      (value "100n")
      (footprint "eagle-import:C0603")
      (libsource (lib "eagle-import") (part "C-EUC0603"))
    )
    (comp (ref "D8")
      (value "N.C.")
      (footprint "eagle-import:SOD123")
      (libsource (lib "eagle-import") (part "SCHOTTKYSOD123"))
    )
    (comp (ref "D9")
      (value "SKL14")
      (footprint "eagle-import:SOD123")
      (libsource (lib "eagle-import") (part "SCHOTTKYSOD123"))
    )
    (comp (ref "D10")
      (value "BAS316")
      (footprint "eagle-import:SOD323-R")
      (libsource (lib "eagle-import") (part "DIODESOD323R"))
    )
    (comp (ref "D11")
      (value "BAS316")
      (footprint "eagle-import:SOD323-R")
      (libsource (lib "eagle-import") (part "DIODESOD323R"))
    )
    (comp (ref "D12")
      (value "BAS316")
      (footprint "eagle-import:SOD323-R")
      (libsource (lib "eagle-import") (part "DIODESOD323R"))
    )
    (comp (ref "D13")
      (value "BAS316")
      (footprint "eagle-import:SOD323-R")
      (libsource (lib "eagle-import") (part "DIODESOD323R"))
    )
    (comp (ref "D14")
      (value "SK55")
      (footprint "eagle-import:SMB")
      (libsource (lib "eagle-import") (part "SCHOTTKYSMB"))
    )
    (comp (ref "IC9")
      (value "TL072D")
      (footprint "eagle-import:SOIC127P600X173-8N")
      (libsource (lib "eagle-import") (part "TL072SOIC8"))
    )
    (comp (ref "IC10")
      (value "TL072D")
      (footprint "eagle-import:SOIC127P600X173-8N")
      (libsource (lib "eagle-import") (part "TL072SOIC8"))
    )
    (comp (ref "IC11")
      (value "LTC2050HVCS8#PBF")
      (footprint "eagle-import:SOIC127P600X173-8N")
      (libsource (lib "eagle-import") (part "OP27GSZSO8"))
    )
    (comp (ref "IC21")
      (value "SN74LVC1G3157DCKR")
      (footprint "eagle-import:SOT65P210X110-6N")
      (libsource (lib "eagle-import") (part "SN74LVC1G3157-DCK"))
    )
    (comp (ref "KK3")
      (value "SK96/84")
      (footprint "eagle-import:SK96_84")
      (libsource (lib "eagle-import") (part "SK96/84"))
    )
    (comp (ref "Q3")
      (value "D45H11FP")
      (footprint "eagle-import:TO220FP-V")
      (libsource (lib "eagle-import") (part "D45H11-FPV"))
    )
    (comp (ref "Q4")
      (value "D45H11FP")
      (footprint "eagle-import:TO220FP-V")
      (libsource (lib "eagle-import") (part "D45H11-FPV"))
    )
    (comp (ref "Q5")
      (value "FQPF11P06 or FQPF27P06")
      (footprint "eagle-import:TO220FP-V")
      (libsource (lib "eagle-import") (part "P-MOSFET-FPV"))
    )
    (comp (ref "Q6")
      (value "BCP56-16.115")
      (footprint "eagle-import:SOT230P700X180-4N")
      (libsource (lib "eagle-import") (part "BCP56"))
    )
    (comp (ref "Q7")
      (value "MMBT5401")
      (footprint "eagle-import:SOT23-BEC")
      (libsource (lib "eagle-import") (part "-PNP-SOT23-BECBC857B"))
    )
    (comp (ref "Q8")
      (value "NZT605")
      (footprint "eagle-import:SOT230P700X180-4N")
      (libsource (lib "eagle-import") (part "NZT605"))
    )
    (comp (ref "Q9")
      (value "BSS205NH6327XTSA1")
      (footprint "eagle-import:SOT103P240X110-3N")
      (fields
        (field (name "MPN") "2N7002-7-F")
        (field (name "MPN_1") "2N7002-7-F")
        (field (name "OC_FARNELL") "1713823")
        (field (name "OC_NEWARK") "25R5679")
        (field (name "PACKAGE") "SOT-23-3")
        (field (name "SUPPLIER") "DIODES INC.")
      )
      (libsource (lib "eagle-import") (part "2N7002"))
    )
    (comp (ref "Q10")
      (value "PSMN0R9-25YLC")
      (footprint "eagle-import:SOT669")
      (libsource (lib "eagle-import") (part "N-MOSFETLFPAK"))
    )
    (comp (ref "Q11")
      (value "PSMN0R9-25YLC")
      (footprint "eagle-import:SOT669")
      (libsource (lib "eagle-import") (part "N-MOSFETLFPAK"))
    )
    (comp (ref "Q27")
      (value "2N7002")
      (footprint "eagle-import:SOT103P240X110-3N")
      (fields (field (name "MPN") "2N7002-7-F"))
      (libsource (lib "eagle-import") (part "2N7002"))
    )
    (comp (ref "R25")
      (value "0R1/2-3W")
      (footprint "eagle-import:R2512")
      (libsource (lib "eagle-import") (part "R-EU_R2512"))
    )
    (comp (ref "R26")
      (value "0R1/2-3W")
      (footprint "eagle-import:R2512")
      (libsource (lib "eagle-import") (part "R-EU_R2512"))
    )
    (comp (ref "R27")
      (value "4K7")
      (footprint "eagle-import:R0805")
      (libsource (lib "eagle-import") (part "R-EU_R0805"))
    )
    (comp (ref "R28")
      (value "N.C.")
      (footprint "eagle-import:R0805")
      (libsource (lib "eagle-import") (part "R-EU_R0805"))
    )
    (comp (ref "R29")
      (value "2R2/2W")
      (footprint "eagle-import:R2512")
      (libsource (lib "eagle-import") (part "R-EU_R2512"))
    )
    (comp (ref "R30")
      (value "4K7")
      (footprint "eagle-import:R0805")
      (libsource (lib "eagle-import") (part "R-EU_R0805"))
    )
    (comp (ref "R31")
      (value "10K")
      (footprint "eagle-import:R0805")
      (libsource (lib "eagle-import") (part "R-EU_R0805"))
    )
    (comp (ref "R32")
      (value "4K7")
      (footprint "eagle-import:R0805")
      (libsource (lib "eagle-import") (part "R-EU_R0805"))
    )
    (comp (ref "R33")
      (value "2K2")
      (footprint "eagle-import:R0805")
      (libsource (lib "eagle-import") (part "R-EU_R0805"))
    )
    (comp (ref "R34")
      (value "10R")
      (footprint "eagle-import:R1206")
      (libsource (lib "eagle-import") (part "R-EU_R1206"))
    )
    (comp (ref "R35")
      (value "10R")
      (footprint "eagle-import:R1206")
      (libsource (lib "eagle-import") (part "R-EU_R1206"))
    )
    (comp (ref "R36")
      (value "4K7")
      (footprint "eagle-import:R0805")
      (libsource (lib "eagle-import") (part "R-EU_R0805"))
    )
    (comp (ref "R37")
      (value "220R")
      (footprint "eagle-import:R0805")
      (libsource (lib "eagle-import") (part "R-EU_R0805"))
    )
    (comp (ref "R38")
      (value "1K")
      (footprint "eagle-import:R0805")
      (libsource (lib "eagle-import") (part "R-EU_R0805"))
    )
    (comp (ref "R39")
      (value "220R")
      (footprint "eagle-import:R0805")
      (libsource (lib "eagle-import") (part "R-EU_R0805"))
    )
    (comp (ref "R40")
      (value "2K2")
      (footprint "eagle-import:R0805")
      (libsource (lib "eagle-import") (part "R-EU_R0805"))
    )
    (comp (ref "R41")
      (value "7K5 0.1%")
      (footprint "eagle-import:R0805")
      (libsource (lib "eagle-import") (part "R-EU_R0805"))
    )
    (comp (ref "R42")
      (value "22K")
      (footprint "eagle-import:R0805")
      (libsource (lib "eagle-import") (part "R-EU_R0805"))
    )
    (comp (ref "R43")
      (value "1K")
      (footprint "eagle-import:R0805")
      (libsource (lib "eagle-import") (part "R-EU_R0805"))
    )
    (comp (ref "R44")
      (value "10K")
      (footprint "eagle-import:R0805")
      (libsource (lib "eagle-import") (part "R-EU_R0805"))
    )
    (comp (ref "R45")
      (value "124K 0.1%")
      (footprint "eagle-import:R0805")
      (libsource (lib "eagle-import") (part "R-EU_R0805"))
    )
    (comp (ref "R46")
      (value "124K 0.1%")
      (footprint "eagle-import:R0805")
      (libsource (lib "eagle-import") (part "R-EU_R0805"))
    )
    (comp (ref "R47")
      (value "10K")
      (footprint "eagle-import:R0805")
      (libsource (lib "eagle-import") (part "R-EU_R0805"))
    )
    (comp (ref "R48")
      (value "2K2")
      (footprint "eagle-import:R0805")
      (libsource (lib "eagle-import") (part "R-EU_R0805"))
    )
    (comp (ref "R49")
      (value "15R")
      (footprint "eagle-import:R2010")
      (libsource (lib "eagle-import") (part "R-EU_R2010"))
    )
    (comp (ref "R50")
      (value "7K5 0.1%")
      (footprint "eagle-import:R0805")
      (libsource (lib "eagle-import") (part "R-EU_R0805"))
    )
    (comp (ref "R51")
      (value "N.C.")
      (footprint "eagle-import:R0805")
      (libsource (lib "eagle-import") (part "R-EU_R0805"))
    )
    (comp (ref "R52")
      (value "10K")
      (footprint "eagle-import:R0805")
      (libsource (lib "eagle-import") (part "R-EU_R0805"))
    )
    (comp (ref "R53")
      (value "10K")
      (footprint "eagle-import:R0805")
      (libsource (lib "eagle-import") (part "R-EU_R0805"))
    )
    (comp (ref "R54")
      (value "220R")
      (footprint "eagle-import:R0805")
      (libsource (lib "eagle-import") (part "R-EU_R0805"))
    )
    (comp (ref "R55")
      (value "100K")
      (footprint "eagle-import:R0805")
      (libsource (lib "eagle-import") (part "R-EU_R0805"))
    )
    (comp (ref "R56")
      (value "2K2")
      (footprint "eagle-import:R0805")
      (libsource (lib "eagle-import") (part "R-EU_R0805"))
    )
    (comp (ref "R57")
      (value "2K2")
      (footprint "eagle-import:R0805")
      (libsource (lib "eagle-import") (part "R-EU_R0805"))
    )
    (comp (ref "R58")
      (value "39K 0.1%")
      (footprint "eagle-import:R0805")
      (libsource (lib "eagle-import") (part "R-EU_R0805"))
    )
    (comp (ref "R59")
      (value "820R 0.1%")
      (footprint "eagle-import:R0805")
      (libsource (lib "eagle-import") (part "R-EU_R0805"))
    )
    (comp (ref "R60")
      (value "47K")
      (footprint "eagle-import:R0805")
      (libsource (lib "eagle-import") (part "R-EU_R0805"))
    )
    (comp (ref "R61")
      (value "1R")
      (footprint "eagle-import:R1206")
      (libsource (lib "eagle-import") (part "R-EU_R1206"))
    )
    (comp (ref "R62")
      (value "47K")
      (footprint "eagle-import:R0805")
      (libsource (lib "eagle-import") (part "R-EU_R0805"))
    )
    (comp (ref "R63")
      (value "8K2")
      (footprint "eagle-import:R0805")
      (libsource (lib "eagle-import") (part "R-EU_R0805"))
    )
    (comp (ref "R64")
      (value "39K 0.1%")
      (footprint "eagle-import:R0805")
      (libsource (lib "eagle-import") (part "R-EU_R0805"))
    )
    (comp (ref "R65")
      (value "47K")
      (footprint "eagle-import:R0805")
      (libsource (lib "eagle-import") (part "R-EU_R0805"))
    )
    (comp (ref "R66")
      (value "3K3")
      (footprint "eagle-import:R0805")
      (libsource (lib "eagle-import") (part "R-EU_R0805"))
    )
    (comp (ref "R67")
      (value "0R010 (low TCR)")
      (footprint "eagle-import:R_2512-4WIRE")
      (libsource (lib "eagle-import") (part "R-EU_4WIRE2512"))
    )
    (comp (ref "R68")
      (value "820R 0.1%")
      (footprint "eagle-import:R0805")
      (libsource (lib "eagle-import") (part "R-EU_R0805"))
    )
    (comp (ref "R115")
      (value "220R")
      (footprint "eagle-import:R0805")
      (libsource (lib "eagle-import") (part "R-EU_R0805"))
    )
    (comp (ref "R116")
      (value "470R")
      (footprint "eagle-import:R0805")
      (libsource (lib "eagle-import") (part "R-EU_R0805"))
    )
    (comp (ref "R118")
      (value "22K")
      (footprint "eagle-import:R0805")
      (libsource (lib "eagle-import") (part "R-EU_R0805"))
    )
    (comp (ref "ZD2")
      (value "MM3Z9V1T1G")
      (footprint "eagle-import:SOD323-R")
      (libsource (lib "eagle-import") (part "ZENER-DIODESOD323R"))
    )
    (comp (ref "C90")
      (value "10n")
      (footprint "eagle-import:C0805")
      (libsource (lib "eagle-import") (part "C-EUC0805"))
    )
    (comp (ref "C91")
      (value "470n")
      (footprint "eagle-import:C0805")
      (libsource (lib "eagle-import") (part "C-EUC0805"))
    )
    (comp (ref "C92")
      (value "HHXC630A330MHA0G")
      (footprint "eagle-import:CAPAE830X1050N")
      (libsource (lib "eagle-import") (part "ECAPSMD8.3MM/HA0"))
    )
    (comp (ref "C93")
      (value "10n/200V")
      (footprint "eagle-import:C1206")
      (libsource (lib "eagle-import") (part "C-EUC1206"))
    )
    (comp (ref "C94")
      (value "N.C.")
      (footprint "eagle-import:ECAP2_5")
      (libsource (lib "eagle-import") (part "ECAP2G/5"))
    )
    (comp (ref "C95")
      (value "N.C.")
      (footprint "eagle-import:C0805")
      (libsource (lib "eagle-import") (part "C-EUC0805"))
    )
    (comp (ref "C96")
      (value "N.C.")
      (footprint "eagle-import:C0805")
      (libsource (lib "eagle-import") (part "C-EUC0805"))
    )
    (comp (ref "C97")
      (value "10n/200V")
      (footprint "eagle-import:C1206")
      (libsource (lib "eagle-import") (part "C-EUC1206"))
    )
    (comp (ref "C98")
      (value "10n")
      (footprint "eagle-import:C0805")
      (libsource (lib "eagle-import") (part "C-EUC0805"))
    )
    (comp (ref "D20")
      (value "BAS316")
      (footprint "eagle-import:SOD323-R")
      (libsource (lib "eagle-import") (part "DIODESOD323R"))
    )
    (comp (ref "F1")
      (value "ZH32")
      (footprint "eagle-import:ZH32")
      (libsource (lib "eagle-import") (part "ZH32"))
    )
    (comp (ref "F2")
      (value "ZH32")
      (footprint "eagle-import:ZH32")
      (libsource (lib "eagle-import") (part "ZH32"))
    )
    (comp (ref "J2")
      (value "FCR7350R")
      (footprint "eagle-import:S16N-PC")
      (libsource (lib "eagle-import") (part "BINDING_POSTCLIFF"))
    )
    (comp (ref "J3")
      (value "FCR7350B")
      (footprint "eagle-import:S16N-PC")
      (libsource (lib "eagle-import") (part "BINDING_POSTCLIFF"))
    )
    (comp (ref "JP3")
      (value "JP2-CUT-0805")
      (footprint "eagle-import:R_0805")
      (libsource (lib "eagle-import") (part "JP2-CUT-0805"))
    )
    (comp (ref "JP4")
      (value "JP2-CUT-0805")
      (footprint "eagle-import:R_0805")
      (libsource (lib "eagle-import") (part "JP2-CUT-0805"))
    )
    (comp (ref "K1")
      (value "G6K-2F-5DC")
      (footprint "eagle-import:G6K-2F")
      (fields
        (field (name "MF") "OMRON COMPONENTS USA")
        (field (name "MPN") "G6K-2F DC24")
        (field (name "MF_1") "OMRON COMPONENTS USA")
        (field (name "MPN_1") "G6K-2F DC24")
        (field (name "OC_FARNELL") "1690427")
        (field (name "OC_NEWARK") "36K7467")
      )
      (libsource (lib "eagle-import") (part "G6K-2F"))
    )
    (comp (ref "Q20")
      (value "MMBT5401")
      (footprint "eagle-import:SOT23-BEC")
      (libsource (lib "eagle-import") (part "-PNP-SOT23-BECBC857B"))
    )
    (comp (ref "Q21")
      (value "MMBT5551")
      (footprint "eagle-import:SOT23-BEC")
      (libsource (lib "eagle-import") (part "-NPN-SOT23-BECMMBT5551LT1"))
    )
    (comp (ref "Q22")
      (value "MMBT5551")
      (footprint "eagle-import:SOT23-BEC")
      (libsource (lib "eagle-import") (part "-NPN-SOT23-BECMMBT5551LT1"))
    )
    (comp (ref "Q23")
      (value "2N7002")
      (footprint "eagle-import:SOT103P240X110-3N")
      (fields
        (field (name "MPN") "2N7002-7-F")
        (field (name "MPN_1") "2N7002-7-F")
        (field (name "OC_FARNELL") "1713823")
        (field (name "OC_NEWARK") "25R5679")
        (field (name "PACKAGE") "SOT-23-3")
        (field (name "SUPPLIER") "DIODES INC.")
      )
      (libsource (lib "eagle-import") (part "2N7002"))
    )
    (comp (ref "R104")
      (value "330R")
      (footprint "eagle-import:R0805")
      (libsource (lib "eagle-import") (part "R-EU_R0805"))
    )
    (comp (ref "R105")
      (value "750R")
      (footprint "eagle-import:R0805")
      (libsource (lib "eagle-import") (part "R-EU_R0805"))
    )
    (comp (ref "R106")
      (value "3K3")
      (footprint "eagle-import:R0805")
      (libsource (lib "eagle-import") (part "R-EU_R0805"))
    )
    (comp (ref "R107")
      (value "10K")
      (footprint "eagle-import:R0805")
      (libsource (lib "eagle-import") (part "R-EU_R0805"))
    )
    (comp (ref "R108")
      (value "10K")
      (footprint "eagle-import:R0805")
      (libsource (lib "eagle-import") (part "R-EU_R0805"))
    )
    (comp (ref "R109")
      (value "1R")
      (footprint "eagle-import:R1206")
      (libsource (lib "eagle-import") (part "R-EU_R1206"))
    )
    (comp (ref "R110")
      (value "750R")
      (footprint "eagle-import:R0805")
      (libsource (lib "eagle-import") (part "R-EU_R0805"))
    )
    (comp (ref "R111")
      (value "47K")
      (footprint "eagle-import:R0805")
      (libsource (lib "eagle-import") (part "R-EU_R0805"))
    )
    (comp (ref "R112")
      (value "330R")
      (footprint "eagle-import:R0805")
      (libsource (lib "eagle-import") (part "R-EU_R0805"))
    )
    (comp (ref "R113")
      (value "470R")
      (footprint "eagle-import:R0805")
      (libsource (lib "eagle-import") (part "R-EU_R0805"))
    )
    (comp (ref "R114")
      (value "100K")
      (footprint "eagle-import:R0805")
      (libsource (lib "eagle-import") (part "R-EU_R0805"))
    )
    (comp (ref "X4")
      (value "DS1024-2*10R0")
      (footprint "eagle-import:SSW-110-02-T-D-RA")
      (libsource (lib "eagle-import") (part "SSW-110-02-T-D-RA"))
    )
    (comp (ref "ZD5")
      (value "SMAJ51A")
      (footprint "eagle-import:DO214AA")
      (libsource (lib "eagle-import") (part "P6SMB68A"))
    )
    (comp (ref "C1")
      (value "10n/200V")
      (footprint "eagle-import:C1206")
      (libsource (lib "eagle-import") (part "C-EUC1206"))
    )
    (comp (ref "C2")
      (value "HHXC630A330MHA0G")
      (footprint "eagle-import:CAPAE830X1050N")
      (libsource (lib "eagle-import") (part "ECAPSMD8.3MM/HA0"))
    )
    (comp (ref "C3")
      (value "10n/200V")
      (footprint "eagle-import:C1206")
      (libsource (lib "eagle-import") (part "C-EUC1206"))
    )
    (comp (ref "C4")
      (value "10n/200V")
      (footprint "eagle-import:C1206")
      (libsource (lib "eagle-import") (part "C-EUC1206"))
    )
    (comp (ref "C5")
      (value "4u7/100V")
      (footprint "eagle-import:C1210")
      (libsource (lib "eagle-import") (part "C-EUC1210"))
    )
    (comp (ref "C6")
      (value "4u7/100V")
      (footprint "eagle-import:C1210")
      (libsource (lib "eagle-import") (part "C-EUC1210"))
    )
    (comp (ref "C7")
      (value "1u/100V")
      (footprint "eagle-import:C1206")
      (libsource (lib "eagle-import") (part "C-EUC1206"))
    )
    (comp (ref "C8")
      (value "470n")
      (footprint "eagle-import:C0805")
      (libsource (lib "eagle-import") (part "C-EUC0805"))
    )
    (comp (ref "C9")
      (value "100n")
      (footprint "eagle-import:C0603")
      (libsource (lib "eagle-import") (part "C-EUC0603"))
    )
    (comp (ref "C10")
      (value "10u")
      (footprint "eagle-import:C1210")
      (libsource (lib "eagle-import") (part "C-EUC1210"))
    )
    (comp (ref "C11")
      (value "EEEFK1J101P")
      (footprint "eagle-import:CAPAE1030X1050N")
      (libsource (lib "eagle-import") (part "ECAP10X10"))
    )
    (comp (ref "C12")
      (value "470p")
      (footprint "eagle-import:C0805")
      (libsource (lib "eagle-import") (part "C-EUC0805"))
    )
    (comp (ref "C13")
      (value "EEEFK1H470P")
      (footprint "eagle-import:CAPAE830X1050N")
      (libsource (lib "eagle-import") (part "ECAPSMD8.3MM/HA0"))
    )
    (comp (ref "C14")
      (value "N.C.")
      (footprint "eagle-import:C0805")
      (libsource (lib "eagle-import") (part "C-EUC0805"))
    )
    (comp (ref "C15")
      (value "10u")
      (footprint "eagle-import:C1210")
      (libsource (lib "eagle-import") (part "C-EUC1210"))
    )
    (comp (ref "C16")
      (value "EEEFK1J101P")
      (footprint "eagle-import:CAPAE1030X1050N")
      (libsource (lib "eagle-import") (part "ECAP10X10"))
    )
    (comp (ref "C17")
      (value "33p")
      (footprint "eagle-import:C0805")
      (libsource (lib "eagle-import") (part "C-EUC0805"))
    )
    (comp (ref "C18")
      (value "6n8")
      (footprint "eagle-import:C0805")
      (libsource (lib "eagle-import") (part "C-EUC0805"))
    )
    (comp (ref "C19")
      (value "470p")
      (footprint "eagle-import:C0805")
      (libsource (lib "eagle-import") (part "C-EUC0805"))
    )
    (comp (ref "D1")
      (value "BAS316")
      (footprint "eagle-import:SOD323-R")
      (libsource (lib "eagle-import") (part "DIODESOD323R"))
    )
    (comp (ref "D2")
      (value "STPS15H100")
      (footprint "eagle-import:TO252-L")
      (libsource (lib "eagle-import") (part "SCHOTTKY-DUAL_A_L"))
    )
    (comp (ref "D3")
      (value "BAS316")
      (footprint "eagle-import:SOD323-R")
      (libsource (lib "eagle-import") (part "DIODESOD323R"))
    )
    (comp (ref "FM1")
      (value "FIDUCIAL_2")
      (footprint "eagle-import:FIDUCIAL_DUAL")
      (libsource (lib "eagle-import") (part "FIDUCIAL_2"))
    )
    (comp (ref "FM2")
      (value "FIDUCIAL_2")
      (footprint "eagle-import:FIDUCIAL_DUAL")
      (libsource (lib "eagle-import") (part "FIDUCIAL_2"))
    )
    (comp (ref "FM3")
      (value "FIDUCIAL_2")
      (footprint "eagle-import:FIDUCIAL_DUAL")
      (libsource (lib "eagle-import") (part "FIDUCIAL_2"))
    )
    (comp (ref "GND")
      (value "PCB_TEST_TABSHIELD")
      (footprint "eagle-import:PCB_SHIELD_TAB")
      (libsource (lib "eagle-import") (part "PCB_TEST_TABSHIELD"))
    )
    (comp (ref "IC1")
      (value "LTC3864EMSE#PBF")
      (footprint "eagle-import:LTC_05-08-1666")
      (libsource (lib "eagle-import") (part "LTC3864"))
    )
    (comp (ref "J1")
      (value "4907")
      (footprint "eagle-import:PCB_TAB-4907")
      (libsource (lib "eagle-import") (part "PCB_TAB-4907"))
    )
    (comp (ref "L1")
      (value "RN112-4-02-0M7")
      (footprint "eagle-import:RN112")
      (libsource (lib "eagle-import") (part "RN112"))
    )
    (comp (ref "L2")
      (value "125CDMCCDS-330MC")
      (footprint "eagle-import:125CDMCC_DS")
      (libsource (lib "eagle-import") (part "125CDMCC/DS"))
    )
    (comp (ref "L3")
      (value "VLS6045AF-3R3N")
      (footprint "eagle-import:COILCRAFT_HPI0630")
      (libsource (lib "eagle-import") (part "COILCRAFT_HPI0630"))
    )
    (comp (ref "OSHWA")
      (value "HR000002")
      (footprint "eagle-import:CERT-SMALL-SILK")
      (libsource (lib "eagle-import") (part "OSHWA-CERT-SMALL"))
    )
    (comp (ref "Q1")
      (value "SUD19P06-60")
      (footprint "eagle-import:TO229P990X239-3N")
      (libsource (lib "eagle-import") (part "P-MOSFETDPAK"))
    )
    (comp (ref "Q2")
      (value "MMBT5401")
      (footprint "eagle-import:SOT23-BEC")
      (libsource (lib "eagle-import") (part "-PNP-SOT23-BECBC857B"))
    )
    (comp (ref "R1")
      (value "N.C.")
      (footprint "eagle-import:R2512")
      (libsource (lib "eagle-import") (part "R-EU_R2512"))
    )
    (comp (ref "R2")
      (value "10K")
      (footprint "eagle-import:R0805")
      (libsource (lib "eagle-import") (part "R-EU_R0805"))
    )
    (comp (ref "R3")
      (value "R008/2-3W")
      (footprint "eagle-import:R2512")
      (libsource (lib "eagle-import") (part "R-EU_R2512"))
    )
    (comp (ref "R4")
      (value "15R")
      (footprint "eagle-import:R2010")
      (libsource (lib "eagle-import") (part "R-EU_R2010"))
    )
    (comp (ref "R5")
      (value "10R")
      (footprint "eagle-import:R1206")
      (libsource (lib "eagle-import") (part "R-EU_R1206"))
    )
    (comp (ref "R6")
      (value "10K")
      (footprint "eagle-import:R0805")
      (libsource (lib "eagle-import") (part "R-EU_R0805"))
    )
    (comp (ref "R7")
      (value "100K")
      (footprint "eagle-import:R0805")
      (libsource (lib "eagle-import") (part "R-EU_R0805"))
    )
    (comp (ref "R8")
      (value "1K")
      (footprint "eagle-import:R0805")
      (libsource (lib "eagle-import") (part "R-EU_R0805"))
    )
    (comp (ref "R9")
      (value "330K")
      (footprint "eagle-import:R0805")
      (libsource (lib "eagle-import") (part "R-EU_R0805"))
    )
    (comp (ref "R10")
      (value "100K")
      (footprint "eagle-import:R0805")
      (libsource (lib "eagle-import") (part "R-EU_R0805"))
    )
    (comp (ref "R11")
      (value "4K7")
      (footprint "eagle-import:R0805")
      (libsource (lib "eagle-import") (part "R-EU_R0805"))
    )
    (comp (ref "SH1")
      (value "SHORTNOHOLE")
      (footprint "eagle-import:SHORT_NOHOLE")
      (libsource (lib "eagle-import") (part "SHORTNOHOLE"))
    )
    (comp (ref "SH2")
      (value "Pgnd to Pout- short")
      (footprint "eagle-import:SHORT_NOHOLE")
      (libsource (lib "eagle-import") (part "SHORTNOHOLE"))
    )
    (comp (ref "SH3")
      (value "Sgnd to Pgnd short")
      (footprint "eagle-import:SHORT_NOHOLE")
      (libsource (lib "eagle-import") (part "SHORTNOHOLE"))
    )
    (comp (ref "X1")
      (value "39-30-1020")
      (footprint "eagle-import:MINIFIT_39301020")
      (libsource (lib "eagle-import") (part "MINIFIT_39301020"))
    )
    (comp (ref "ZD1")
      (value "SMAJ51A")
      (footprint "eagle-import:DO214AA")
      (libsource (lib "eagle-import") (part "P6SMB68A"))
    )
  )
  (nets
    (net (code "1") (name "+3V3") (class "Default")
      (node (ref "C30") (pin "1") (pinfunction "1_1") (pintype "passive"))
      (node (ref "C35") (pin "1") (pinfunction "1_1") (pintype "passive"))
      (node (ref "C38") (pin "2") (pinfunction "2_2") (pintype "passive"))
      (node (ref "IC3") (pin "1") (pinfunction "VDD1_1") (pintype "passive"))
      (node (ref "IC3") (pin "7") (pinfunction "EN1_7") (pintype "input"))
      (node (ref "IC7") (pin "1") (pinfunction "VDD1_1") (pintype "passive"))
      (node (ref "IC7") (pin "7") (pinfunction "EN1_7") (pintype "input"))
      (node (ref "IC8") (pin "8") (pinfunction "VCC_8") (pintype "power_in"))
      (node (ref "R22") (pin "1") (pinfunction "1_1") (pintype "passive"))
      (node (ref "R23") (pin "1") (pinfunction "1_1") (pintype "passive"))
      (node (ref "R24") (pin "1") (pinfunction "1_1") (pintype "passive"))
      (node (ref "X2") (pin "1") (pinfunction "1_1") (pintype "passive"))
    )
    (net (code "2") (name "+5V") (class "Default")
      (node (ref "C31") (pin "2") (pinfunction "2_2") (pintype "passive"))
      (node (ref "C32") (pin "1") (pinfunction "1_1") (pintype "passive"))
      (node (ref "C36") (pin "2") (pinfunction "2_2") (pintype "passive"))
      (node (ref "C63") (pin "2") (pinfunction "2_2") (pintype "passive"))
      (node (ref "C64") (pin "2") (pinfunction "2_2") (pintype "passive"))
      (node (ref "C65") (pin "2") (pinfunction "2_2") (pintype "passive"))
      (node (ref "C66") (pin "1") (pinfunction "1_1") (pintype "passive"))
      (node (ref "C68") (pin "1") (pinfunction "1_1") (pintype "passive"))
      (node (ref "C79") (pin "2") (pinfunction "2_2") (pintype "passive"))
      (node (ref "C80") (pin "2") (pinfunction "2_2") (pintype "passive"))
      (node (ref "D20") (pin "C") (pinfunction "C_C") (pintype "passive"))
      (node (ref "FB2") (pin "P$2") (pinfunction "2_P$2") (pintype "passive"))
      (node (ref "IC12") (pin "7") (pinfunction "~{PRE}_7") (pintype "input"))
      (node (ref "IC12") (pin "8") (pinfunction "VDD_8") (pintype "power_in"))
      (node (ref "IC13") (pin "9") (pinfunction "VDD_9") (pintype "power_in"))
      (node (ref "IC15") (pin "5") (pinfunction "VDD_5") (pintype "passive"))
      (node (ref "IC18") (pin "13") (pinfunction "DVDD_13") (pintype "power_in"))
      (node (ref "IC3") (pin "10") (pinfunction "EN2_10") (pintype "input"))
      (node (ref "IC3") (pin "16") (pinfunction "VDD2_16") (pintype "passive"))
      (node (ref "IC4") (pin "8") (pinfunction "VCC_8") (pintype "passive"))
      (node (ref "IC7") (pin "10") (pinfunction "EN2_10") (pintype "input"))
      (node (ref "IC7") (pin "16") (pinfunction "VDD2_16") (pintype "passive"))
      (node (ref "K1") (pin "1") (pinfunction "+_1") (pintype "passive"))
      (node (ref "LED2") (pin "TA") (pinfunction "A_TA") (pintype "passive"))
      (node (ref "LED3") (pin "BA") (pinfunction "A_BA") (pintype "passive"))
      (node (ref "LED3") (pin "TA") (pinfunction "A_TA") (pintype "passive"))
      (node (ref "Q12") (pin "2") (pinfunction "S_2") (pintype "passive"))
      (node (ref "R107") (pin "2") (pinfunction "2_2") (pintype "passive"))
      (node (ref "R17") (pin "1") (pinfunction "1_1") (pintype "passive"))
      (node (ref "R69") (pin "1") (pinfunction "1_1") (pintype "passive"))
      (node (ref "R70") (pin "1") (pinfunction "1_1") (pintype "passive"))
      (node (ref "R71") (pin "1") (pinfunction "1_1") (pintype "passive"))
      (node (ref "R72") (pin "1") (pinfunction "1_1") (pintype "passive"))
      (node (ref "R84") (pin "2") (pinfunction "2_2") (pintype "passive"))
      (node (ref "R98") (pin "2") (pinfunction "2_2") (pintype "passive"))
    )
    (net (code "3") (name "+VNR") (class "Default")
      (node (ref "C27") (pin "1") (pinfunction "1_1") (pintype "passive"))
      (node (ref "IC5") (pin "8") (pinfunction "VI_8") (pintype "input"))
      (node (ref "R14") (pin "1") (pinfunction "1_1") (pintype "passive"))
    )
    (net (code "4") (name "+VREF") (class "Default")
      (node (ref "C69") (pin "+") (pinfunction "+_+") (pintype "passive"))
      (node (ref "C73") (pin "2") (pinfunction "2_2") (pintype "passive"))
      (node (ref "C83") (pin "2") (pinfunction "2_2") (pintype "passive"))
      (node (ref "IC14") (pin "6") (pinfunction "VOUT_6") (pintype "output"))
      (node (ref "IC16") (pin "2") (pinfunction "VREF_2") (pintype "input"))
      (node (ref "IC18") (pin "9") (pinfunction "REFP0_9") (pintype "input"))
      (node (ref "R31") (pin "1") (pinfunction "1_1") (pintype "passive"))
    )
    (net (code "5") (name "-9V") (class "Default")
      (node (ref "C21") (pin "1") (pinfunction "1_1") (pintype "passive"))
      (node (ref "IC6") (pin "2") (pinfunction "IN_2") (pintype "input"))
      (node (ref "IC6") (pin "3") (pinfunction "IN_3") (pintype "input"))
      (node (ref "IC6") (pin "6") (pinfunction "IN_6") (pintype "input"))
      (node (ref "IC6") (pin "7") (pinfunction "IN_7") (pintype "input"))
      (node (ref "R12") (pin "1") (pinfunction "1_1") (pintype "passive"))
      (node (ref "R28") (pin "1") (pinfunction "1_1") (pintype "passive"))
      (node (ref "R38") (pin "2") (pinfunction "2_2") (pintype "passive"))
      (node (ref "R39") (pin "2") (pinfunction "2_2") (pintype "passive"))
    )
    (net (code "6") (name "AUX_USET_SW") (class "Default")
      (node (ref "IC13") (pin "4") (pinfunction "GPB3_4") (pintype "bidirectional"))
      (node (ref "IC17") (pin "6") (pinfunction "CTRL_6") (pintype "input"))
      (node (ref "LED2") (pin "BA") (pinfunction "A_BA") (pintype "passive"))
    )
    (net (code "7") (name "CC_ACTIVE") (class "Default")
      (node (ref "IC13") (pin "22") (pinfunction "GPA1_22") (pintype "bidirectional"))
      (node (ref "Q16") (pin "1") (pinfunction "G_1") (pintype "passive"))
      (node (ref "Q27") (pin "1") (pinfunction "G_1") (pintype "passive"))
      (node (ref "R100") (pin "2") (pinfunction "2_2") (pintype "passive"))
      (node (ref "R98") (pin "1") (pinfunction "1_1") (pintype "passive"))
    )
    (net (code "8") (name "CSA") (class "Default")
      (node (ref "IC3") (pin "13") (pinfunction "B2_13") (pintype "output"))
      (node (ref "IC4") (pin "1") (pinfunction "A_1") (pintype "input"))
    )
    (net (code "9") (name "CSB") (class "Default")
      (node (ref "IC3") (pin "12") (pinfunction "B3_12") (pintype "output"))
      (node (ref "IC4") (pin "2") (pinfunction "B_2") (pintype "input"))
    )
    (net (code "10") (name "CS_ADC") (class "Default")
      (node (ref "IC18") (pin "2") (pinfunction "~{CS}_2") (pintype "input"))
      (node (ref "RN1") (pin "7") (pinfunction "2_7") (pintype "passive"))
    )
    (net (code "11") (name "CS_DAC") (class "Default")
      (node (ref "IC16") (pin "5") (pinfunction "~{SYNC}_5") (pintype "input"))
      (node (ref "RN1") (pin "8") (pinfunction "2_8") (pintype "passive"))
    )
    (net (code "12") (name "CS_IOEXP") (class "Default")
      (node (ref "IC13") (pin "11") (pinfunction "~{CS}_11") (pintype "input"))
      (node (ref "RN1") (pin "6") (pinfunction "2_6") (pintype "passive"))
    )
    (net (code "13") (name "CURR_5A") (class "Default")
      (node (ref "IC13") (pin "28") (pinfunction "GPA7_28") (pintype "bidirectional"))
      (node (ref "IC21") (pin "6") (pinfunction "CTRL_6") (pintype "input"))
      (node (ref "Q11") (pin "4") (pinfunction "G_4") (pintype "passive"))
      (node (ref "R65") (pin "2") (pinfunction "2_2") (pintype "passive"))
    )
    (net (code "14") (name "CURR_50MA") (class "Default")
      (node (ref "IC13") (pin "27") (pinfunction "GPA6_27") (pintype "bidirectional"))
      (node (ref "Q10") (pin "4") (pinfunction "G_4") (pintype "passive"))
      (node (ref "R60") (pin "2") (pinfunction "2_2") (pintype "passive"))
    )
    (net (code "15") (name "CV_ACTIVE") (class "Default")
      (node (ref "IC13") (pin "23") (pinfunction "GPA2_23") (pintype "bidirectional"))
      (node (ref "Q15") (pin "1") (pinfunction "G_1") (pintype "passive"))
      (node (ref "R84") (pin "1") (pinfunction "1_1") (pintype "passive"))
      (node (ref "R88") (pin "2") (pinfunction "2_2") (pintype "passive"))
    )
    (net (code "16") (name "DC+") (class "Default")
      (node (ref "C1") (pin "2") (pinfunction "2_2") (pintype "passive"))
      (node (ref "L1") (pin "1") (pinfunction "1_1") (pintype "passive"))
      (node (ref "R1") (pin "2") (pinfunction "2_2") (pintype "passive"))
      (node (ref "X1") (pin "1") (pinfunction "1_1") (pintype "passive"))
    )
    (net (code "17") (name "DC-") (class "Default")
      (node (ref "C1") (pin "1") (pinfunction "1_1") (pintype "passive"))
      (node (ref "L1") (pin "3") (pinfunction "1_3") (pintype "passive"))
      (node (ref "R1") (pin "1") (pinfunction "1_1") (pintype "passive"))
      (node (ref "X1") (pin "2") (pinfunction "1_2") (pintype "passive"))
    )
    (net (code "18") (name "DC_OUT") (class "Default")
      (node (ref "C2") (pin "+") (pinfunction "+_+") (pintype "passive"))
      (node (ref "C22") (pin "1") (pinfunction "1_1") (pintype "passive"))
      (node (ref "C23") (pin "1") (pinfunction "1_1") (pintype "passive"))
      (node (ref "C4") (pin "2") (pinfunction "2_2") (pintype "passive"))
      (node (ref "C5") (pin "1") (pinfunction "1_1") (pintype "passive"))
      (node (ref "C6") (pin "1") (pinfunction "1_1") (pintype "passive"))
      (node (ref "C7") (pin "1") (pinfunction "1_1") (pintype "passive"))
      (node (ref "C8") (pin "2") (pinfunction "2_2") (pintype "passive"))
      (node (ref "IC1") (pin "11") (pinfunction "VIN_11") (pintype "passive"))
      (node (ref "IC2") (pin "2") (pinfunction "VIN_2") (pintype "power_in"))
      (node (ref "L1") (pin "2") (pinfunction "2_2") (pintype "passive"))
      (node (ref "R13") (pin "2") (pinfunction "2_2") (pintype "passive"))
      (node (ref "R3") (pin "1") (pinfunction "1_1") (pintype "passive"))
      (node (ref "ZD1") (pin "C") (pinfunction "C_C") (pintype "passive"))
    )
    (net (code "19") (name "DIB_A0") (class "Default")
      (node (ref "IC8") (pin "1") (pinfunction "A0_1") (pintype "input"))
      (node (ref "R24") (pin "2") (pinfunction "2_2") (pintype "passive"))
      (node (ref "X2") (pin "17") (pinfunction "1_17") (pintype "passive"))
    )
    (net (code "20") (name "DIB_A1") (class "Default")
      (node (ref "IC8") (pin "2") (pinfunction "A1_2") (pintype "input"))
      (node (ref "R23") (pin "2") (pinfunction "2_2") (pintype "passive"))
      (node (ref "X2") (pin "19") (pinfunction "1_19") (pintype "passive"))
    )
    (net (code "21") (name "DIB_A2") (class "Default")
      (node (ref "IC8") (pin "3") (pinfunction "A2_3") (pintype "input"))
      (node (ref "R22") (pin "2") (pinfunction "2_2") (pintype "passive"))
      (node (ref "X2") (pin "18") (pinfunction "1_18") (pintype "passive"))
    )
    (net (code "22") (name "DIB_CSA") (class "Default")
      (node (ref "IC3") (pin "4") (pinfunction "A2_4") (pintype "input"))
      (node (ref "X2") (pin "9") (pinfunction "1_9") (pintype "passive"))
    )
    (net (code "23") (name "DIB_CSB") (class "Default")
      (node (ref "IC3") (pin "5") (pinfunction "A3_5") (pintype "input"))
      (node (ref "X2") (pin "12") (pinfunction "1_12") (pintype "passive"))
    )
    (net (code "24") (name "DIB_IRQ") (class "Default")
      (node (ref "IC7") (pin "6") (pinfunction "A4_6") (pintype "output"))
      (node (ref "X2") (pin "10") (pinfunction "1_10") (pintype "passive"))
    )
    (net (code "25") (name "DIB_MISO") (class "Default")
      (node (ref "IC3") (pin "6") (pinfunction "A4_6") (pintype "output"))
      (node (ref "X2") (pin "14") (pinfunction "1_14") (pintype "passive"))
    )
    (net (code "26") (name "DIB_MOSI") (class "Default")
      (node (ref "IC7") (pin "3") (pinfunction "A1_3") (pintype "input"))
      (node (ref "X2") (pin "15") (pinfunction "1_15") (pintype "passive"))
    )
    (net (code "27") (name "DIB_NRESET") (class "Default")
      (node (ref "IC7") (pin "5") (pinfunction "A3_5") (pintype "input"))
      (node (ref "X2") (pin "4") (pinfunction "1_4") (pintype "passive"))
    )
    (net (code "28") (name "DIB_SCL") (class "Default")
      (node (ref "IC8") (pin "6") (pinfunction "SCL_6") (pintype "bidirectional"))
      (node (ref "X2") (pin "5") (pinfunction "1_5") (pintype "passive"))
    )
    (net (code "29") (name "DIB_SCLK") (class "Default")
      (node (ref "IC3") (pin "3") (pinfunction "A1_3") (pintype "input"))
      (node (ref "X2") (pin "13") (pinfunction "1_13") (pintype "passive"))
    )
    (net (code "30") (name "DIB_SDA") (class "Default")
      (node (ref "IC8") (pin "5") (pinfunction "SDA_5") (pintype "bidirectional"))
      (node (ref "X2") (pin "8") (pinfunction "1_8") (pintype "passive"))
    )
    (net (code "31") (name "FB") (class "Default")
      (node (ref "C19") (pin "1") (pinfunction "1_1") (pintype "passive"))
      (node (ref "IC1") (pin "5") (pinfunction "VFB_5") (pintype "input"))
      (node (ref "Q2") (pin "C") (pinfunction "C_C") (pintype "passive"))
      (node (ref "R11") (pin "1") (pinfunction "1_1") (pintype "passive"))
      (node (ref "R9") (pin "2") (pinfunction "2_2") (pintype "passive"))
    )
    (net (code "32") (name "GCOM") (class "Default")
      (node (ref "IC10") (pin "6") (pinfunction "-IN_6") (pintype "input"))
      (node (ref "IC10") (pin "7") (pinfunction "OUT_7") (pintype "output"))
      (node (ref "R41") (pin "1") (pinfunction "1_1") (pintype "passive"))
      (node (ref "R58") (pin "1") (pinfunction "1_1") (pintype "passive"))
    )
    (net (code "33") (name "GND") (class "Default")
      (node (ref "C20") (pin "2") (pinfunction "2_2") (pintype "passive"))
      (node (ref "C21") (pin "2") (pinfunction "2_2") (pintype "passive"))
      (node (ref "C22") (pin "2") (pinfunction "2_2") (pintype "passive"))
      (node (ref "C23") (pin "2") (pinfunction "2_2") (pintype "passive"))
      (node (ref "C26") (pin "2") (pinfunction "2_2") (pintype "passive"))
      (node (ref "C27") (pin "2") (pinfunction "2_2") (pintype "passive"))
      (node (ref "C28") (pin "2") (pinfunction "2_2") (pintype "passive"))
      (node (ref "C29") (pin "1") (pinfunction "1_1") (pintype "passive"))
      (node (ref "C31") (pin "1") (pinfunction "1_1") (pintype "passive"))
      (node (ref "C32") (pin "2") (pinfunction "2_2") (pintype "passive"))
      (node (ref "C33") (pin "1") (pinfunction "1_1") (pintype "passive"))
      (node (ref "C34") (pin "2") (pinfunction "2_2") (pintype "passive"))
      (node (ref "C36") (pin "1") (pinfunction "1_1") (pintype "passive"))
      (node (ref "C37") (pin "1") (pinfunction "1_1") (pintype "passive"))
      (node (ref "C39") (pin "2") (pinfunction "2_2") (pintype "passive"))
      (node (ref "C42") (pin "2") (pinfunction "2_2") (pintype "passive"))
      (node (ref "C48") (pin "2") (pinfunction "2_2") (pintype "passive"))
      (node (ref "C49") (pin "1") (pinfunction "1_1") (pintype "passive"))
      (node (ref "C50") (pin "2") (pinfunction "2_2") (pintype "passive"))
      (node (ref "C51") (pin "1") (pinfunction "1_1") (pintype "passive"))
      (node (ref "C52") (pin "1") (pinfunction "1_1") (pintype "passive"))
      (node (ref "C53") (pin "1") (pinfunction "1_1") (pintype "passive"))
      (node (ref "C54") (pin "1") (pinfunction "1_1") (pintype "passive"))
      (node (ref "C56") (pin "1") (pinfunction "1_1") (pintype "passive"))
      (node (ref "C57") (pin "2") (pinfunction "2_2") (pintype "passive"))
      (node (ref "C58") (pin "1") (pinfunction "1_1") (pintype "passive"))
      (node (ref "C59") (pin "1") (pinfunction "1_1") (pintype "passive"))
      (node (ref "C62") (pin "2") (pinfunction "2_2") (pintype "passive"))
      (node (ref "C65") (pin "1") (pinfunction "1_1") (pintype "passive"))
      (node (ref "C66") (pin "2") (pinfunction "2_2") (pintype "passive"))
      (node (ref "C67") (pin "2") (pinfunction "2_2") (pintype "passive"))
      (node (ref "C68") (pin "2") (pinfunction "2_2") (pintype "passive"))
      (node (ref "C69") (pin "-") (pinfunction "-_-") (pintype "passive"))
      (node (ref "C70") (pin "2") (pinfunction "2_2") (pintype "passive"))
      (node (ref "C71") (pin "2") (pinfunction "2_2") (pintype "passive"))
      (node (ref "C72") (pin "1") (pinfunction "1_1") (pintype "passive"))
      (node (ref "C73") (pin "1") (pinfunction "1_1") (pintype "passive"))
      (node (ref "C74") (pin "2") (pinfunction "2_2") (pintype "passive"))
      (node (ref "C75") (pin "1") (pinfunction "1_1") (pintype "passive"))
      (node (ref "C76") (pin "1") (pinfunction "1_1") (pintype "passive"))
      (node (ref "C77") (pin "2") (pinfunction "2_2") (pintype "passive"))
      (node (ref "C78") (pin "1") (pinfunction "1_1") (pintype "passive"))
      (node (ref "C79") (pin "1") (pinfunction "1_1") (pintype "passive"))
      (node (ref "C80") (pin "1") (pinfunction "1_1") (pintype "passive"))
      (node (ref "C81") (pin "1") (pinfunction "1_1") (pintype "passive"))
      (node (ref "C82") (pin "1") (pinfunction "1_1") (pintype "passive"))
      (node (ref "C83") (pin "1") (pinfunction "1_1") (pintype "passive"))
      (node (ref "C84") (pin "2") (pinfunction "2_2") (pintype "passive"))
      (node (ref "C85") (pin "1") (pinfunction "1_1") (pintype "passive"))
      (node (ref "C86") (pin "1") (pinfunction "1_1") (pintype "passive"))
      (node (ref "C88") (pin "1") (pinfunction "1_1") (pintype "passive"))
      (node (ref "C89") (pin "1") (pinfunction "1_1") (pintype "passive"))
      (node (ref "D10") (pin "C") (pinfunction "C_C") (pintype "passive"))
      (node (ref "D17") (pin "A") (pinfunction "A_A") (pintype "passive"))
      (node (ref "D19") (pin "C") (pinfunction "C_C") (pintype "passive"))
      (node (ref "D5") (pin "A") (pinfunction "A_A") (pintype "passive"))
      (node (ref "D6") (pin "A") (pinfunction "A_A") (pintype "passive"))
      (node (ref "D7") (pin "C") (pinfunction "C_C") (pintype "passive"))
      (node (ref "D9") (pin "C") (pinfunction "C_C") (pintype "passive"))
      (node (ref "GND") (pin "1") (pinfunction "P$1_1") (pintype "bidirectional"))
      (node (ref "IC12") (pin "4") (pinfunction "VSS_4") (pintype "power_in"))
      (node (ref "IC13") (pin "10") (pinfunction "VSS_10") (pintype "power_in"))
      (node (ref "IC13") (pin "15") (pinfunction "A0_15") (pintype "input"))
      (node (ref "IC13") (pin "16") (pinfunction "A1_16") (pintype "input"))
      (node (ref "IC13") (pin "17") (pinfunction "A2_17") (pintype "input"))
      (node (ref "IC14") (pin "4") (pinfunction "GND_4") (pintype "passive"))
      (node (ref "IC15") (pin "2") (pinfunction "GND_2") (pintype "passive"))
      (node (ref "IC16") (pin "8") (pinfunction "GND_8") (pintype "power_in"))
      (node (ref "IC17") (pin "2") (pinfunction "GND_2") (pintype "passive"))
      (node (ref "IC18") (pin "3") (pinfunction "CLK_3") (pintype "bidirectional"))
      (node (ref "IC18") (pin "4") (pinfunction "DGND_4") (pintype "passive"))
      (node (ref "IC18") (pin "5") (pinfunction "AVSS_5") (pintype "passive"))
      (node (ref "IC18") (pin "8") (pinfunction "REFN0_8") (pintype "input"))
      (node (ref "IC2") (pin "9") (pinfunction "GND_9") (pintype "passive"))
      (node (ref "IC2") (pin "TP") (pinfunction "TP_TP") (pintype "passive"))
      (node (ref "IC20") (pin "4") (pinfunction "GND_4") (pintype "passive"))
      (node (ref "IC21") (pin "2") (pinfunction "GND_2") (pintype "passive"))
      (node (ref "IC3") (pin "15") (pinfunction "GND2_15") (pintype "passive"))
      (node (ref "IC3") (pin "9") (pinfunction "GND2_2_9") (pintype "passive"))
      (node (ref "IC4") (pin "4") (pinfunction "GND_4") (pintype "passive"))
      (node (ref "IC5") (pin "2") (pinfunction "GND_2") (pintype "passive"))
      (node (ref "IC5") (pin "3") (pinfunction "GND_3") (pintype "passive"))
      (node (ref "IC5") (pin "6") (pinfunction "GND_6") (pintype "passive"))
      (node (ref "IC5") (pin "7") (pinfunction "GND_7") (pintype "passive"))
      (node (ref "IC6") (pin "5") (pinfunction "GND_5") (pintype "passive"))
      (node (ref "IC7") (pin "15") (pinfunction "GND2_15") (pintype "passive"))
      (node (ref "IC7") (pin "9") (pinfunction "GND2_2_9") (pintype "passive"))
      (node (ref "KK3") (pin "1") (pinfunction "1_1") (pintype "passive"))
      (node (ref "KK3") (pin "2") (pinfunction "2_2") (pintype "passive"))
      (node (ref "Q15") (pin "2") (pinfunction "S_2") (pintype "passive"))
      (node (ref "Q16") (pin "2") (pinfunction "S_2") (pintype "passive"))
      (node (ref "Q17") (pin "2") (pinfunction "S_2") (pintype "passive"))
      (node (ref "Q21") (pin "E") (pinfunction "E_E") (pintype "passive"))
      (node (ref "Q23") (pin "2") (pinfunction "S_2") (pintype "passive"))
      (node (ref "Q27") (pin "2") (pinfunction "S_2") (pintype "passive"))
      (node (ref "Q9") (pin "2") (pinfunction "S_2") (pintype "passive"))
      (node (ref "R111") (pin "1") (pinfunction "1_1") (pintype "passive"))
      (node (ref "R114") (pin "1") (pinfunction "1_1") (pintype "passive"))
      (node (ref "R15") (pin "1") (pinfunction "1_1") (pintype "passive"))
      (node (ref "R16") (pin "1") (pinfunction "1_1") (pintype "passive"))
      (node (ref "R19") (pin "1") (pinfunction "1_1") (pintype "passive"))
      (node (ref "R21") (pin "1") (pinfunction "1_1") (pintype "passive"))
      (node (ref "R37") (pin "2") (pinfunction "2_2") (pintype "passive"))
      (node (ref "R55") (pin "1") (pinfunction "1_1") (pintype "passive"))
      (node (ref "R60") (pin "1") (pinfunction "1_1") (pintype "passive"))
      (node (ref "R65") (pin "1") (pinfunction "1_1") (pintype "passive"))
      (node (ref "R73") (pin "2") (pinfunction "2_2") (pintype "passive"))
      (node (ref "R79") (pin "1") (pinfunction "1_1") (pintype "passive"))
      (node (ref "R87") (pin "1") (pinfunction "1_1") (pintype "passive"))
      (node (ref "R89") (pin "2") (pinfunction "2_2") (pintype "passive"))
      (node (ref "R96") (pin "1") (pinfunction "1_1") (pintype "passive"))
      (node (ref "R97") (pin "1") (pinfunction "1_1") (pintype "passive"))
      (node (ref "SH1") (pin "2") (pinfunction "GND_B_2") (pintype "bidirectional"))
      (node (ref "TR1") (pin "4") (pinfunction "4_4") (pintype "passive"))
      (node (ref "X3") (pin "2") (pinfunction "1_2") (pintype "passive"))
      (node (ref "ZD3") (pin "1") (pinfunction "A_1") (pintype "passive"))
      (node (ref "ZD3") (pin "2") (pinfunction "A_2") (pintype "passive"))
    )
    (net (code "34") (name "GNDIO") (class "Default")
      (node (ref "C30") (pin "2") (pinfunction "2_2") (pintype "passive"))
      (node (ref "C35") (pin "2") (pinfunction "2_2") (pintype "passive"))
      (node (ref "C38") (pin "1") (pinfunction "1_1") (pintype "passive"))
      (node (ref "IC3") (pin "2") (pinfunction "GND1_2_2") (pintype "passive"))
      (node (ref "IC3") (pin "8") (pinfunction "GND1_8") (pintype "passive"))
      (node (ref "IC7") (pin "2") (pinfunction "GND1_2_2") (pintype "passive"))
      (node (ref "IC7") (pin "8") (pinfunction "GND1_8") (pintype "passive"))
      (node (ref "IC8") (pin "4") (pinfunction "GND_4") (pintype "passive"))
      (node (ref "IC8") (pin "7") (pinfunction "WP_7") (pintype "input"))
      (node (ref "X2") (pin "11") (pinfunction "1_11") (pintype "passive"))
      (node (ref "X2") (pin "16") (pinfunction "1_16") (pintype "passive"))
      (node (ref "X2") (pin "20") (pinfunction "1_20") (pintype "passive"))
      (node (ref "X2") (pin "25") (pinfunction "1_25") (pintype "passive"))
      (node (ref "X2") (pin "7") (pinfunction "1_7") (pintype "passive"))
    )
    (net (code "35") (name "IRQ") (class "Default")
      (node (ref "IC13") (pin "20") (pinfunction "INTA_20") (pintype "output"))
      (node (ref "IC7") (pin "11") (pinfunction "B4_11") (pintype "input"))
    )
    (net (code "36") (name "ISENSE+") (class "Default")
      (node (ref "IC11") (pin "3") (pinfunction "+IN_3") (pintype "input"))
      (node (ref "R58") (pin "2") (pinfunction "2_2") (pintype "passive"))
      (node (ref "R59") (pin "2") (pinfunction "2_2") (pintype "passive"))
    )
    (net (code "37") (name "ISENSE-") (class "Default")
      (node (ref "IC11") (pin "2") (pinfunction "-IN_2") (pintype "input"))
      (node (ref "R64") (pin "1") (pinfunction "1_1") (pintype "passive"))
      (node (ref "R68") (pin "2") (pinfunction "2_2") (pintype "passive"))
    )
    (net (code "38") (name "I_MON") (class "Default")
      (node (ref "D17") (pin "C") (pinfunction "C_C") (pintype "passive"))
      (node (ref "IC21") (pin "4") (pinfunction "COM_4") (pintype "bidirectional"))
      (node (ref "R115") (pin "1") (pinfunction "1_1") (pintype "passive"))
      (node (ref "R62") (pin "1") (pinfunction "1_1") (pintype "passive"))
      (node (ref "R64") (pin "2") (pinfunction "2_2") (pintype "passive"))
      (node (ref "R81") (pin "1") (pinfunction "1_1") (pintype "passive"))
    )
    (net (code "39") (name "I_SERVO") (class "Default")
      (node (ref "C55") (pin "2") (pinfunction "2_2") (pintype "passive"))
      (node (ref "C60") (pin "2") (pinfunction "2_2") (pintype "passive"))
      (node (ref "D13") (pin "C") (pinfunction "C_C") (pintype "passive"))
      (node (ref "IC10") (pin "1") (pinfunction "OUT_1") (pintype "output"))
      (node (ref "R99") (pin "1") (pinfunction "1_1") (pintype "passive"))
    )
    (net (code "40") (name "I_SET") (class "Default")
      (node (ref "I_SET") (pin "2") (pinfunction "2_2") (pintype "passive"))
      (node (ref "R57") (pin "1") (pinfunction "1_1") (pintype "passive"))
      (node (ref "R77") (pin "1") (pinfunction "1_1") (pintype "passive"))
    )
    (net (code "41") (name "LOOP_CTRL") (class "Default")
      (node (ref "D12") (pin "A") (pinfunction "A_A") (pintype "passive"))
      (node (ref "D13") (pin "A") (pinfunction "A_A") (pintype "passive"))
      (node (ref "R40") (pin "1") (pinfunction "1_1") (pintype "passive"))
      (node (ref "R43") (pin "1") (pinfunction "1_1") (pintype "passive"))
      (node (ref "R94") (pin "2") (pinfunction "2_2") (pintype "passive"))
    )
    (net (code "42") (name "MISO") (class "Default")
      (node (ref "IC13") (pin "14") (pinfunction "SO_14") (pintype "output"))
      (node (ref "IC15") (pin "4") (pinfunction "SI/O_4") (pintype "bidirectional"))
      (node (ref "IC18") (pin "15") (pinfunction "DOUT/~{DRDY}_15") (pintype "output"))
      (node (ref "RN2") (pin "7") (pinfunction "2_7") (pintype "passive"))
    )
    (net (code "43") (name "MOSI") (class "Default")
      (node (ref "IC13") (pin "13") (pinfunction "SI_13") (pintype "input"))
      (node (ref "IC16") (pin "7") (pinfunction "DIN_7") (pintype "input"))
      (node (ref "IC18") (pin "16") (pinfunction "DIN_16") (pintype "input"))
      (node (ref "RN2") (pin "6") (pinfunction "2_6") (pintype "passive"))
    )
    (net (code "44") (name "Net-(C10-Pad1)") (class "Default")
      (node (ref "C10") (pin "1") (pinfunction "1_1") (pintype "passive"))
      (node (ref "C11") (pin "+") (pinfunction "+_+") (pintype "passive"))
      (node (ref "C15") (pin "1") (pinfunction "1_1") (pintype "passive"))
      (node (ref "C16") (pin "+") (pinfunction "+_+") (pintype "passive"))
      (node (ref "L2") (pin "2") (pinfunction "2_2") (pintype "passive"))
      (node (ref "L3") (pin "1") (pinfunction "1_1") (pintype "passive"))
      (node (ref "R4") (pin "1") (pinfunction "1_1") (pintype "passive"))
      (node (ref "R6") (pin "1") (pinfunction "1_1") (pintype "passive"))
      (node (ref "R7") (pin "1") (pinfunction "1_1") (pintype "passive"))
      (node (ref "R9") (pin "1") (pinfunction "1_1") (pintype "passive"))
    )
    (net (code "45") (name "Net-(C12-Pad2)") (class "Default")
      (node (ref "C12") (pin "2") (pinfunction "2_2") (pintype "passive"))
      (node (ref "R5") (pin "2") (pinfunction "2_2") (pintype "passive"))
    )
    (net (code "46") (name "Net-(C18-Pad1)") (class "Default")
      (node (ref "C18") (pin "1") (pinfunction "1_1") (pintype "passive"))
      (node (ref "R8") (pin "1") (pinfunction "1_1") (pintype "passive"))
    )
    (net (code "47") (name "Net-(C19-Pad2)") (class "Default")
      (node (ref "C19") (pin "2") (pinfunction "2_2") (pintype "passive"))
      (node (ref "D3") (pin "A") (pinfunction "A_A") (pintype "passive"))
      (node (ref "Q2") (pin "B") (pinfunction "B_B") (pintype "passive"))
      (node (ref "R10") (pin "1") (pinfunction "1_1") (pintype "passive"))
      (node (ref "R7") (pin "2") (pinfunction "2_2") (pintype "passive"))
    )
    (net (code "48") (name "Net-(C20-Pad1)") (class "Default")
      (node (ref "C20") (pin "1") (pinfunction "1_1") (pintype "passive"))
      (node (ref "D4") (pin "A") (pinfunction "A_A") (pintype "passive"))
      (node (ref "R12") (pin "2") (pinfunction "2_2") (pintype "passive"))
    )
    (net (code "49") (name "Net-(C25-Pad2)") (class "Default")
      (node (ref "C25") (pin "2") (pinfunction "2_2") (pintype "passive"))
      (node (ref "R15") (pin "2") (pinfunction "2_2") (pintype "passive"))
    )
    (net (code "50") (name "Net-(C26-Pad1)") (class "Default")
      (node (ref "C26") (pin "1") (pinfunction "1_1") (pintype "passive"))
      (node (ref "R14") (pin "2") (pinfunction "2_2") (pintype "passive"))
      (node (ref "R18") (pin "2") (pinfunction "2_2") (pintype "passive"))
      (node (ref "TR1") (pin "3") (pinfunction "3_3") (pintype "passive"))
    )
    (net (code "51") (name "Net-(C33-Pad2)") (class "Default")
      (node (ref "C33") (pin "2") (pinfunction "2_2") (pintype "passive"))
      (node (ref "R20") (pin "1") (pinfunction "1_1") (pintype "passive"))
    )
    (net (code "52") (name "Net-(C40-Pad1)") (class "Default")
      (node (ref "C40") (pin "1") (pinfunction "1_1") (pintype "passive"))
      (node (ref "D10") (pin "A") (pinfunction "A_A") (pintype "passive"))
      (node (ref "Q7") (pin "B") (pinfunction "B_B") (pintype "passive"))
      (node (ref "R42") (pin "2") (pinfunction "2_2") (pintype "passive"))
    )
    (net (code "53") (name "Net-(C40-Pad2)") (class "Default")
      (node (ref "C40") (pin "2") (pinfunction "2_2") (pintype "passive"))
      (node (ref "Q7") (pin "C") (pinfunction "C_C") (pintype "passive"))
      (node (ref "R36") (pin "2") (pinfunction "2_2") (pintype "passive"))
    )
    (net (code "54") (name "Net-(C41-Pad2)") (class "Default")
      (node (ref "C41") (pin "2") (pinfunction "2_2") (pintype "passive"))
      (node (ref "R44") (pin "1") (pinfunction "1_1") (pintype "passive"))
    )
    (net (code "55") (name "Net-(C42-Pad1)") (class "Default")
      (node (ref "C42") (pin "1") (pinfunction "1_1") (pintype "passive"))
      (node (ref "R118") (pin "2") (pinfunction "2_2") (pintype "passive"))
      (node (ref "R47") (pin "1") (pinfunction "1_1") (pintype "passive"))
      (node (ref "R48") (pin "2") (pinfunction "2_2") (pintype "passive"))
    )
    (net (code "56") (name "Net-(C44-Pad1)") (class "Default")
      (node (ref "C44") (pin "1") (pinfunction "1_1") (pintype "passive"))
      (node (ref "R51") (pin "2") (pinfunction "2_2") (pintype "passive"))
    )
    (net (code "57") (name "Net-(C47-Pad2)") (class "Default")
      (node (ref "C47") (pin "2") (pinfunction "2_2") (pintype "passive"))
      (node (ref "R53") (pin "1") (pinfunction "1_1") (pintype "passive"))
    )
    (net (code "58") (name "Net-(C48-Pad1)") (class "Default")
      (node (ref "C48") (pin "1") (pinfunction "1_1") (pintype "passive"))
      (node (ref "R56") (pin "1") (pinfunction "1_1") (pintype "passive"))
      (node (ref "R57") (pin "2") (pinfunction "2_2") (pintype "passive"))
    )
    (net (code "59") (name "Net-(C55-Pad1)") (class "Default")
      (node (ref "C55") (pin "1") (pinfunction "1_1") (pintype "passive"))
      (node (ref "R63") (pin "1") (pinfunction "1_1") (pintype "passive"))
    )
    (net (code "60") (name "Net-(C61-Pad2)") (class "Default")
      (node (ref "C61") (pin "2") (pinfunction "2_2") (pintype "passive"))
      (node (ref "R66") (pin "1") (pinfunction "1_1") (pintype "passive"))
    )
    (net (code "61") (name "Net-(C90-Pad2)") (class "Default")
      (node (ref "C90") (pin "2") (pinfunction "2_2") (pintype "passive"))
      (node (ref "Q20") (pin "B") (pinfunction "B_B") (pintype "passive"))
      (node (ref "R104") (pin "1") (pinfunction "1_1") (pintype "passive"))
      (node (ref "R105") (pin "2") (pinfunction "2_2") (pintype "passive"))
      (node (ref "R106") (pin "2") (pinfunction "2_2") (pintype "passive"))
    )
    (net (code "62") (name "Net-(C91-Pad2)") (class "Default")
      (node (ref "C91") (pin "2") (pinfunction "2_2") (pintype "passive"))
      (node (ref "R109") (pin "2") (pinfunction "2_2") (pintype "passive"))
    )
    (net (code "63") (name "Net-(C98-Pad1)") (class "Default")
      (node (ref "C98") (pin "1") (pinfunction "1_1") (pintype "passive"))
      (node (ref "Q22") (pin "B") (pinfunction "B_B") (pintype "passive"))
      (node (ref "R110") (pin "1") (pinfunction "1_1") (pintype "passive"))
      (node (ref "R112") (pin "2") (pinfunction "2_2") (pintype "passive"))
    )
    (net (code "64") (name "Net-(D2-C)") (class "Default")
      (node (ref "C12") (pin "1") (pinfunction "1_1") (pintype "passive"))
      (node (ref "D2") (pin "3") (pinfunction "C_3") (pintype "passive"))
      (node (ref "L2") (pin "1") (pinfunction "1_1") (pintype "passive"))
      (node (ref "Q1") (pin "2") (pinfunction "D_2") (pintype "passive"))
    )
    (net (code "65") (name "Net-(D3-PadC)") (class "Default")
      (node (ref "D3") (pin "C") (pinfunction "C_C") (pintype "passive"))
      (node (ref "Q2") (pin "E") (pinfunction "E_E") (pintype "passive"))
      (node (ref "R6") (pin "2") (pinfunction "2_2") (pintype "passive"))
    )
    (net (code "66") (name "Net-(D4-PadC)") (class "Default")
      (node (ref "D4") (pin "C") (pinfunction "C_C") (pintype "passive"))
      (node (ref "TR1") (pin "2") (pinfunction "2_2") (pintype "passive"))
    )
    (net (code "67") (name "Net-(D18-PadA)") (class "Default")
      (node (ref "D18") (pin "A") (pinfunction "A_A") (pintype "passive"))
      (node (ref "Q14") (pin "B") (pinfunction "B_B") (pintype "passive"))
      (node (ref "R91") (pin "1") (pinfunction "1_1") (pintype "passive"))
      (node (ref "R96") (pin "2") (pinfunction "2_2") (pintype "passive"))
    )
    (net (code "68") (name "Net-(D18-PadC)") (class "Default")
      (node (ref "D18") (pin "C") (pinfunction "C_C") (pintype "passive"))
      (node (ref "D19") (pin "A") (pinfunction "A_A") (pintype "passive"))
    )
    (net (code "69") (name "Net-(FB1-1)") (class "Default")
      (node (ref "C34") (pin "1") (pinfunction "1_1") (pintype "passive"))
      (node (ref "D6") (pin "C") (pinfunction "C_C") (pintype "passive"))
      (node (ref "FB1") (pin "P$1") (pinfunction "1_P$1") (pintype "passive"))
      (node (ref "FB2") (pin "P$1") (pinfunction "1_P$1") (pintype "passive"))
      (node (ref "IC5") (pin "1") (pinfunction "VO_1") (pintype "passive"))
    )
    (net (code "70") (name "Net-(FB3-1)") (class "Default")
      (node (ref "C37") (pin "2") (pinfunction "2_2") (pintype "passive"))
      (node (ref "D7") (pin "A") (pinfunction "A_A") (pintype "passive"))
      (node (ref "FB3") (pin "P$1") (pinfunction "1_P$1") (pintype "passive"))
      (node (ref "IC6") (pin "1") (pinfunction "OUT_1") (pintype "passive"))
    )
    (net (code "71") (name "Net-(IC1-CAP)") (class "Default")
      (node (ref "C8") (pin "1") (pinfunction "1_1") (pintype "passive"))
      (node (ref "IC1") (pin "9") (pinfunction "CAP_9") (pintype "passive"))
    )
    (net (code "72") (name "Net-(IC1-GATE)") (class "Default")
      (node (ref "IC1") (pin "12") (pinfunction "GATE_12") (pintype "output"))
      (node (ref "Q1") (pin "1") (pinfunction "G_1") (pintype "passive"))
    )
    (net (code "73") (name "Net-(IC1-ITH)") (class "Default")
      (node (ref "C17") (pin "1") (pinfunction "1_1") (pintype "passive"))
      (node (ref "IC1") (pin "6") (pinfunction "ITH_6") (pintype "bidirectional"))
      (node (ref "R8") (pin "2") (pinfunction "2_2") (pintype "passive"))
    )
    (net (code "74") (name "Net-(IC1-RUN)") (class "Default")
      (node (ref "D1") (pin "C") (pinfunction "C_C") (pintype "passive"))
      (node (ref "IC1") (pin "8") (pinfunction "RUN_8") (pintype "input"))
      (node (ref "R2") (pin "2") (pinfunction "2_2") (pintype "passive"))
    )
    (net (code "75") (name "Net-(IC1-SENSE)") (class "Default")
      (node (ref "IC1") (pin "10") (pinfunction "SENSE_10") (pintype "input"))
      (node (ref "Q1") (pin "3") (pinfunction "S_3") (pintype "passive"))
      (node (ref "R3") (pin "2") (pinfunction "2_2") (pintype "passive"))
    )
    (net (code "76") (name "Net-(IC1-SS)") (class "Default")
      (node (ref "C9") (pin "2") (pinfunction "2_2") (pintype "passive"))
      (node (ref "IC1") (pin "4") (pinfunction "SS_4") (pintype "input"))
    )
    (net (code "77") (name "Net-(IC2-BOOT)") (class "Default")
      (node (ref "C24") (pin "2") (pinfunction "2_2") (pintype "passive"))
      (node (ref "IC2") (pin "1") (pinfunction "BOOT_1") (pintype "output"))
    )
    (net (code "78") (name "Net-(IC2-COMP)") (class "Default")
      (node (ref "C29") (pin "2") (pinfunction "2_2") (pintype "passive"))
      (node (ref "IC2") (pin "8") (pinfunction "COMP_8") (pintype "output"))
      (node (ref "R20") (pin "2") (pinfunction "2_2") (pintype "passive"))
    )
    (net (code "79") (name "Net-(IC2-EN)") (class "Default")
      (node (ref "IC2") (pin "3") (pinfunction "EN_3") (pintype "input"))
      (node (ref "R13") (pin "1") (pinfunction "1_1") (pintype "passive"))
      (node (ref "R16") (pin "2") (pinfunction "2_2") (pintype "passive"))
    )
    (net (code "80") (name "Net-(IC2-PH)") (class "Default")
      (node (ref "C24") (pin "1") (pinfunction "1_1") (pintype "passive"))
      (node (ref "C25") (pin "1") (pinfunction "1_1") (pintype "passive"))
      (node (ref "D5") (pin "C") (pinfunction "C_C") (pintype "passive"))
      (node (ref "IC2") (pin "10") (pinfunction "PH_10") (pintype "input"))
      (node (ref "TR1") (pin "1") (pinfunction "1_1") (pintype "passive"))
    )
    (net (code "81") (name "Net-(IC2-RT{slash}CLK)") (class "Default")
      (node (ref "IC2") (pin "5") (pinfunction "RT/CLK_5") (pintype "input"))
      (node (ref "R19") (pin "2") (pinfunction "2_2") (pintype "passive"))
    )
    (net (code "82") (name "Net-(IC2-SS{slash}TR)") (class "Default")
      (node (ref "C28") (pin "1") (pinfunction "1_1") (pintype "passive"))
      (node (ref "IC2") (pin "4") (pinfunction "SS/TR_4") (pintype "input"))
    )
    (net (code "83") (name "Net-(IC2-VSENSE)") (class "Default")
      (node (ref "IC2") (pin "7") (pinfunction "VSENSE_7") (pintype "input"))
      (node (ref "R18") (pin "1") (pinfunction "1_1") (pintype "passive"))
      (node (ref "R21") (pin "2") (pinfunction "2_2") (pintype "passive"))
    )
    (net (code "84") (name "Net-(IC3-B1)") (class "Default")
      (node (ref "IC3") (pin "14") (pinfunction "B1_14") (pintype "output"))
      (node (ref "RN2") (pin "1") (pinfunction "1_1") (pintype "passive"))
    )
    (net (code "85") (name "Net-(IC3-B4)") (class "Default")
      (node (ref "IC3") (pin "11") (pinfunction "B4_11") (pintype "input"))
      (node (ref "RN2") (pin "2") (pinfunction "1_2") (pintype "passive"))
    )
    (net (code "86") (name "Net-(IC4-Y0)") (class "Default")
      (node (ref "IC4") (pin "7") (pinfunction "Y0_7") (pintype "output"))
      (node (ref "RN1") (pin "1") (pinfunction "1_1") (pintype "passive"))
    )
    (net (code "87") (name "Net-(IC4-Y1)") (class "Default")
      (node (ref "IC4") (pin "6") (pinfunction "Y1_6") (pintype "output"))
      (node (ref "RN1") (pin "2") (pinfunction "1_2") (pintype "passive"))
    )
    (net (code "88") (name "Net-(IC4-Y2)") (class "Default")
      (node (ref "IC4") (pin "5") (pinfunction "Y2_5") (pintype "output"))
      (node (ref "RN1") (pin "3") (pinfunction "1_3") (pintype "passive"))
    )
    (net (code "89") (name "Net-(IC4-Y3)") (class "Default")
      (node (ref "IC4") (pin "3") (pinfunction "Y3_3") (pintype "output"))
      (node (ref "RN1") (pin "4") (pinfunction "1_4") (pintype "passive"))
    )
    (net (code "90") (name "Net-(IC7-B1)") (class "Default")
      (node (ref "IC7") (pin "14") (pinfunction "B1_14") (pintype "output"))
      (node (ref "RN2") (pin "3") (pinfunction "1_3") (pintype "passive"))
    )
    (net (code "91") (name "Net-(IC7-B2)") (class "Default")
      (node (ref "IC7") (pin "13") (pinfunction "B2_13") (pintype "output"))
      (node (ref "RN2") (pin "4") (pinfunction "1_4") (pintype "passive"))
    )
    (net (code "92") (name "Net-(IC9A-+IN)") (class "Default")
      (node (ref "IC9") (pin "3") (pinfunction "+IN_3") (pintype "input"))
      (node (ref "R44") (pin "2") (pinfunction "2_2") (pintype "passive"))
      (node (ref "R47") (pin "2") (pinfunction "2_2") (pintype "passive"))
    )
    (net (code "93") (name "Net-(IC9A--IN)") (class "Default")
      (node (ref "C46") (pin "1") (pinfunction "1_1") (pintype "passive"))
      (node (ref "IC9") (pin "2") (pinfunction "-IN_2") (pintype "input"))
      (node (ref "R51") (pin "1") (pinfunction "1_1") (pintype "passive"))
      (node (ref "R52") (pin "2") (pinfunction "2_2") (pintype "passive"))
      (node (ref "R53") (pin "2") (pinfunction "2_2") (pintype "passive"))
    )
    (net (code "94") (name "Net-(IC9B-+IN)") (class "Default")
      (node (ref "IC9") (pin "5") (pinfunction "+IN_5") (pintype "input"))
      (node (ref "R41") (pin "2") (pinfunction "2_2") (pintype "passive"))
      (node (ref "R45") (pin "1") (pinfunction "1_1") (pintype "passive"))
    )
    (net (code "95") (name "Net-(IC9B--IN)") (class "Default")
      (node (ref "C43") (pin "1") (pinfunction "1_1") (pintype "passive"))
      (node (ref "IC9") (pin "6") (pinfunction "-IN_6") (pintype "input"))
      (node (ref "R46") (pin "1") (pinfunction "1_1") (pintype "passive"))
      (node (ref "R50") (pin "2") (pinfunction "2_2") (pintype "passive"))
    )
    (net (code "96") (name "Net-(IC10A-+IN)") (class "Default")
      (node (ref "IC10") (pin "3") (pinfunction "+IN_3") (pintype "input"))
      (node (ref "R56") (pin "2") (pinfunction "2_2") (pintype "passive"))
    )
    (net (code "97") (name "Net-(IC10A--IN)") (class "Default")
      (node (ref "C60") (pin "1") (pinfunction "1_1") (pintype "passive"))
      (node (ref "IC10") (pin "2") (pinfunction "-IN_2") (pintype "input"))
      (node (ref "R116") (pin "2") (pinfunction "2_2") (pintype "passive"))
      (node (ref "R62") (pin "2") (pinfunction "2_2") (pintype "passive"))
      (node (ref "R63") (pin "2") (pinfunction "2_2") (pintype "passive"))
      (node (ref "R66") (pin "2") (pinfunction "2_2") (pintype "passive"))
    )
    (net (code "98") (name "Net-(IC10B-+IN)") (class "Default")
      (node (ref "C39") (pin "1") (pinfunction "1_1") (pintype "passive"))
      (node (ref "IC10") (pin "5") (pinfunction "+IN_5") (pintype "input"))
      (node (ref "R31") (pin "2") (pinfunction "2_2") (pintype "passive"))
      (node (ref "R37") (pin "1") (pinfunction "1_1") (pintype "passive"))
    )
    (net (code "99") (name "Net-(IC11A-OUT)") (class "Default")
      (node (ref "IC11") (pin "6") (pinfunction "OUT_6") (pintype "output"))
      (node (ref "R115") (pin "2") (pinfunction "2_2") (pintype "passive"))
    )
    (net (code "100") (name "Net-(IC12A-~{CLR})") (class "Default")
      (node (ref "D15") (pin "A") (pinfunction "A_A") (pintype "passive"))
      (node (ref "D16") (pin "A") (pinfunction "A_A") (pintype "passive"))
      (node (ref "IC12") (pin "6") (pinfunction "~{CLR}_6") (pintype "input"))
      (node (ref "R71") (pin "2") (pinfunction "2_2") (pintype "passive"))
    )
    (net (code "101") (name "Net-(IC13-~{RESET})") (class "Default")
      (node (ref "C63") (pin "1") (pinfunction "1_1") (pintype "passive"))
      (node (ref "IC13") (pin "18") (pinfunction "~{RESET}_18") (pintype "input"))
      (node (ref "JP1") (pin "2") (pinfunction "2_2") (pintype "passive"))
      (node (ref "R69") (pin "2") (pinfunction "2_2") (pintype "passive"))
    )
    (net (code "102") (name "Net-(IC14-TRIM{slash}NR)") (class "Default")
      (node (ref "C71") (pin "1") (pinfunction "1_1") (pintype "passive"))
      (node (ref "IC14") (pin "5") (pinfunction "TRIM/NR_5") (pintype "input"))
    )
    (net (code "103") (name "Net-(IC16-VOUTA)") (class "Default")
      (node (ref "IC16") (pin "4") (pinfunction "VOUTA_4") (pintype "output"))
      (node (ref "I_SET") (pin "1") (pinfunction "1_1") (pintype "passive"))
    )
    (net (code "104") (name "Net-(IC16-VOUTB)") (class "Default")
      (node (ref "IC16") (pin "3") (pinfunction "VOUTB_3") (pintype "output"))
      (node (ref "U_SET") (pin "1") (pinfunction "1_1") (pintype "passive"))
    )
    (net (code "105") (name "Net-(IC17-NO)") (class "Default")
      (node (ref "IC17") (pin "1") (pinfunction "NO_1") (pintype "bidirectional"))
      (node (ref "R75") (pin "1") (pinfunction "1_1") (pintype "passive"))
      (node (ref "ZD3") (pin "3") (pinfunction "C_3") (pintype "passive"))
    )
    (net (code "106") (name "Net-(IC18-AIN0{slash}REFP1)") (class "Default")
      (node (ref "C78") (pin "2") (pinfunction "2_2") (pintype "passive"))
      (node (ref "IC18") (pin "11") (pinfunction "AIN0/REFP1_11") (pintype "input"))
      (node (ref "R80") (pin "2") (pinfunction "2_2") (pintype "passive"))
    )
    (net (code "107") (name "Net-(IC18-AIN1)") (class "Default")
      (node (ref "C75") (pin "2") (pinfunction "2_2") (pintype "passive"))
      (node (ref "IC18") (pin "10") (pinfunction "AIN1_10") (pintype "input"))
      (node (ref "R77") (pin "2") (pinfunction "2_2") (pintype "passive"))
    )
    (net (code "108") (name "Net-(IC18-AIN2)") (class "Default")
      (node (ref "C76") (pin "2") (pinfunction "2_2") (pintype "passive"))
      (node (ref "IC18") (pin "7") (pinfunction "AIN2_7") (pintype "input"))
      (node (ref "R78") (pin "2") (pinfunction "2_2") (pintype "passive"))
    )
    (net (code "109") (name "Net-(IC18-AIN3{slash}REFN1)") (class "Default")
      (node (ref "C77") (pin "1") (pinfunction "1_1") (pintype "passive"))
      (node (ref "IC18") (pin "6") (pinfunction "AIN3/REFN1_6") (pintype "input"))
      (node (ref "R81") (pin "2") (pinfunction "2_2") (pintype "passive"))
    )
    (net (code "110") (name "Net-(IC18-AVDD)") (class "Default")
      (node (ref "C81") (pin "2") (pinfunction "2_2") (pintype "passive"))
      (node (ref "C82") (pin "2") (pinfunction "2_2") (pintype "passive"))
      (node (ref "IC18") (pin "12") (pinfunction "AVDD_12") (pintype "power_in"))
      (node (ref "R82") (pin "2") (pinfunction "2_2") (pintype "passive"))
    )
    (net (code "111") (name "Net-(IC19A-+IN)") (class "Default")
      (node (ref "IC19") (pin "3") (pinfunction "+IN_3") (pintype "input"))
      (node (ref "IC19") (pin "5") (pinfunction "+IN_5") (pintype "input"))
      (node (ref "R94") (pin "1") (pinfunction "1_1") (pintype "passive"))
    )
    (net (code "112") (name "Net-(IC19A--IN)") (class "Default")
      (node (ref "IC19") (pin "2") (pinfunction "-IN_2") (pintype "input"))
      (node (ref "R86") (pin "2") (pinfunction "2_2") (pintype "passive"))
    )
    (net (code "113") (name "Net-(IC19A-OUT)") (class "Default")
      (node (ref "IC19") (pin "1") (pinfunction "OUT_1") (pintype "output"))
      (node (ref "R88") (pin "1") (pinfunction "1_1") (pintype "passive"))
    )
    (net (code "114") (name "Net-(IC19B--IN)") (class "Default")
      (node (ref "IC19") (pin "6") (pinfunction "-IN_6") (pintype "input"))
      (node (ref "R99") (pin "2") (pinfunction "2_2") (pintype "passive"))
    )
    (net (code "115") (name "Net-(IC19B-OUT)") (class "Default")
      (node (ref "IC19") (pin "7") (pinfunction "OUT_7") (pintype "output"))
      (node (ref "R100") (pin "1") (pinfunction "1_1") (pintype "passive"))
    )
    (net (code "116") (name "Net-(IC20-+IN)") (class "Default")
      (node (ref "C86") (pin "2") (pinfunction "2_2") (pintype "passive"))
      (node (ref "C87") (pin "1") (pinfunction "1_1") (pintype "passive"))
      (node (ref "IC20") (pin "2") (pinfunction "+IN_2") (pintype "input"))
      (node (ref "R83") (pin "2") (pinfunction "2_2") (pintype "passive"))
      (node (ref "R89") (pin "1") (pinfunction "1_1") (pintype "passive"))
    )
    (net (code "117") (name "Net-(IC20--IN)") (class "Default")
      (node (ref "C87") (pin "2") (pinfunction "2_2") (pintype "passive"))
      (node (ref "IC20") (pin "3") (pinfunction "-IN_3") (pintype "input"))
      (node (ref "R95") (pin "2") (pinfunction "2_2") (pintype "passive"))
    )
    (net (code "118") (name "Net-(IC20-OUT)") (class "Default")
      (node (ref "IC20") (pin "7") (pinfunction "OUT_7") (pintype "output"))
      (node (ref "Q17") (pin "1") (pinfunction "G_1") (pintype "passive"))
      (node (ref "R101") (pin "2") (pinfunction "2_2") (pintype "passive"))
      (node (ref "R91") (pin "2") (pinfunction "2_2") (pintype "passive"))
    )
    (net (code "119") (name "Net-(IC21-NO)") (class "Default")
      (node (ref "IC21") (pin "1") (pinfunction "NO_1") (pintype "bidirectional"))
      (node (ref "R116") (pin "1") (pinfunction "1_1") (pintype "passive"))
    )
    (net (code "120") (name "Net-(K1A--)") (class "Default")
      (node (ref "D20") (pin "A") (pinfunction "A_A") (pintype "passive"))
      (node (ref "K1") (pin "8") (pinfunction "-_8") (pintype "passive"))
      (node (ref "Q23") (pin "3") (pinfunction "D_3") (pintype "passive"))
      (node (ref "R113") (pin "1") (pinfunction "1_1") (pintype "passive"))
    )
    (net (code "121") (name "Net-(K1B-S)") (class "Default")
      (node (ref "K1") (pin "4") (pinfunction "S_4") (pintype "passive"))
      (node (ref "X3") (pin "4") (pinfunction "1_4") (pintype "passive"))
    )
    (net (code "122") (name "Net-(K1C-S)") (class "Default")
      (node (ref "K1") (pin "5") (pinfunction "S_5") (pintype "passive"))
      (node (ref "X3") (pin "5") (pinfunction "1_5") (pintype "passive"))
    )
    (net (code "123") (name "Net-(LED1-C)") (class "Default")
      (node (ref "LED1") (pin "CC") (pinfunction "C_CC") (pintype "passive"))
      (node (ref "R73") (pin "1") (pinfunction "1_1") (pintype "passive"))
    )
    (net (code "124") (name "Net-(LED2A-C)") (class "Default")
      (node (ref "LED2") (pin "BC") (pinfunction "C_BC") (pintype "passive"))
      (node (ref "R79") (pin "2") (pinfunction "2_2") (pintype "passive"))
    )
    (net (code "125") (name "Net-(LED2B-C)") (class "Default")
      (node (ref "LED2") (pin "TC") (pinfunction "C_TC") (pintype "passive"))
      (node (ref "R113") (pin "2") (pinfunction "2_2") (pintype "passive"))
    )
    (net (code "126") (name "Net-(LED3A-C)") (class "Default")
      (node (ref "LED3") (pin "BC") (pinfunction "C_BC") (pintype "passive"))
      (node (ref "R92") (pin "2") (pinfunction "2_2") (pintype "passive"))
    )
    (net (code "127") (name "Net-(LED3B-C)") (class "Default")
      (node (ref "LED3") (pin "TC") (pinfunction "C_TC") (pintype "passive"))
      (node (ref "R90") (pin "1") (pinfunction "1_1") (pintype "passive"))
    )
    (net (code "128") (name "Net-(Q3-B)") (class "Default")
      (node (ref "Q3") (pin "1") (pinfunction "B_1") (pintype "passive"))
      (node (ref "R34") (pin "2") (pinfunction "2_2") (pintype "passive"))
    )
    (net (code "129") (name "Net-(Q3-E)") (class "Default")
      (node (ref "Q3") (pin "3") (pinfunction "E_3") (pintype "passive"))
      (node (ref "R25") (pin "2") (pinfunction "2_2") (pintype "passive"))
    )
    (net (code "130") (name "Net-(Q4-B)") (class "Default")
      (node (ref "Q4") (pin "1") (pinfunction "B_1") (pintype "passive"))
      (node (ref "R35") (pin "2") (pinfunction "2_2") (pintype "passive"))
    )
    (net (code "131") (name "Net-(Q4-E)") (class "Default")
      (node (ref "Q4") (pin "3") (pinfunction "E_3") (pintype "passive"))
      (node (ref "R26") (pin "2") (pinfunction "2_2") (pintype "passive"))
    )
    (net (code "132") (name "Net-(Q5-G)") (class "Default")
      (node (ref "Q5") (pin "1") (pinfunction "G_1") (pintype "passive"))
      (node (ref "Q6") (pin "2") (pinfunction "C_2") (pintype "passive"))
      (node (ref "Q6") (pin "4") (pinfunction "C_4") (pintype "passive"))
      (node (ref "R30") (pin "2") (pinfunction "2_2") (pintype "passive"))
      (node (ref "ZD2") (pin "A") (pinfunction "A_A") (pintype "passive"))
    )
    (net (code "133") (name "Net-(Q5-S)") (class "Default")
      (node (ref "Q5") (pin "3") (pinfunction "S_3") (pintype "passive"))
      (node (ref "R29") (pin "1") (pinfunction "1_1") (pintype "passive"))
    )
    (net (code "134") (name "Net-(Q6-B)") (class "Default")
      (node (ref "Q6") (pin "1") (pinfunction "B_1") (pintype "passive"))
      (node (ref "R36") (pin "1") (pinfunction "1_1") (pintype "passive"))
      (node (ref "R38") (pin "1") (pinfunction "1_1") (pintype "passive"))
    )
    (net (code "135") (name "Net-(Q6-E)") (class "Default")
      (node (ref "Q6") (pin "3") (pinfunction "E_3") (pintype "passive"))
      (node (ref "R39") (pin "1") (pinfunction "1_1") (pintype "passive"))
    )
    (net (code "136") (name "Net-(Q8-B)") (class "Default")
      (node (ref "D11") (pin "C") (pinfunction "C_C") (pintype "passive"))
      (node (ref "Q8") (pin "1") (pinfunction "B_1") (pintype "passive"))
      (node (ref "R43") (pin "2") (pinfunction "2_2") (pintype "passive"))
    )
    (net (code "137") (name "Net-(Q8-C-Pad2)") (class "Default")
      (node (ref "Q8") (pin "2") (pinfunction "C_2") (pintype "passive"))
      (node (ref "Q8") (pin "4") (pinfunction "C_4") (pintype "passive"))
      (node (ref "R33") (pin "1") (pinfunction "1_1") (pintype "passive"))
      (node (ref "R34") (pin "1") (pinfunction "1_1") (pintype "passive"))
      (node (ref "R35") (pin "1") (pinfunction "1_1") (pintype "passive"))
    )
    (net (code "138") (name "Net-(Q8-E)") (class "Default")
      (node (ref "D11") (pin "A") (pinfunction "A_A") (pintype "passive"))
      (node (ref "Q8") (pin "3") (pinfunction "E_3") (pintype "passive"))
      (node (ref "R49") (pin "2") (pinfunction "2_2") (pintype "passive"))
    )
    (net (code "139") (name "Net-(Q9-D)") (class "Default")
      (node (ref "C45") (pin "2") (pinfunction "2_2") (pintype "passive"))
      (node (ref "Q9") (pin "3") (pinfunction "D_3") (pintype "passive"))
      (node (ref "R49") (pin "1") (pinfunction "1_1") (pintype "passive"))
    )
    (net (code "140") (name "Net-(Q9-G)") (class "Default")
      (node (ref "C45") (pin "1") (pinfunction "1_1") (pintype "passive"))
      (node (ref "Q9") (pin "1") (pinfunction "G_1") (pintype "passive"))
      (node (ref "R54") (pin "1") (pinfunction "1_1") (pintype "passive"))
      (node (ref "R55") (pin "2") (pinfunction "2_2") (pintype "passive"))
    )
    (net (code "141") (name "Net-(Q10-S-Pad1)") (class "Default")
      (node (ref "Q10") (pin "1") (pinfunction "S_1") (pintype "passive"))
      (node (ref "Q10") (pin "2") (pinfunction "S_2") (pintype "passive"))
      (node (ref "Q10") (pin "3") (pinfunction "S_3") (pintype "passive"))
      (node (ref "R59") (pin "1") (pinfunction "1_1") (pintype "passive"))
      (node (ref "R61") (pin "1") (pinfunction "1_1") (pintype "passive"))
    )
    (net (code "142") (name "Net-(Q11-S-Pad1)") (class "Default")
      (node (ref "Q11") (pin "1") (pinfunction "S_1") (pintype "passive"))
      (node (ref "Q11") (pin "2") (pinfunction "S_2") (pintype "passive"))
      (node (ref "Q11") (pin "3") (pinfunction "S_3") (pintype "passive"))
      (node (ref "R67") (pin "2") (pinfunction "2_2") (pintype "passive"))
    )
    (net (code "143") (name "Net-(Q12-D)") (class "Default")
      (node (ref "Q12") (pin "3") (pinfunction "D_3") (pintype "passive"))
      (node (ref "R74") (pin "2") (pinfunction "2_2") (pintype "passive"))
    )
    (net (code "144") (name "Net-(Q13-PadA2)") (class "Default")
      (node (ref "Q13") (pin "A2") (pinfunction "A2_A2") (pintype "passive"))
      (node (ref "R93") (pin "2") (pinfunction "2_2") (pintype "passive"))
    )
    (net (code "145") (name "Net-(Q13-PadG)") (class "Default")
      (node (ref "Q13") (pin "G") (pinfunction "G_G") (pintype "passive"))
      (node (ref "Q14") (pin "C") (pinfunction "C_C") (pintype "passive"))
      (node (ref "R85") (pin "1") (pinfunction "1_1") (pintype "passive"))
    )
    (net (code "146") (name "Net-(Q14-PadE)") (class "Default")
      (node (ref "Q14") (pin "E") (pinfunction "E_E") (pintype "passive"))
      (node (ref "R97") (pin "2") (pinfunction "2_2") (pintype "passive"))
    )
    (net (code "147") (name "Net-(Q15-D)") (class "Default")
      (node (ref "Q15") (pin "3") (pinfunction "D_3") (pintype "passive"))
      (node (ref "R90") (pin "2") (pinfunction "2_2") (pintype "passive"))
    )
    (net (code "148") (name "Net-(Q16-D)") (class "Default")
      (node (ref "Q16") (pin "3") (pinfunction "D_3") (pintype "passive"))
      (node (ref "R92") (pin "1") (pinfunction "1_1") (pintype "passive"))
    )
    (net (code "149") (name "Net-(Q18-G)") (class "Default")
      (node (ref "Q18") (pin "4") (pinfunction "G_4") (pintype "passive"))
      (node (ref "Q19") (pin "C") (pinfunction "C_C") (pintype "passive"))
      (node (ref "R101") (pin "1") (pinfunction "1_1") (pintype "passive"))
    )
    (net (code "150") (name "Net-(Q19-PadB)") (class "Default")
      (node (ref "Q19") (pin "B") (pinfunction "B_B") (pintype "passive"))
      (node (ref "R102") (pin "1") (pinfunction "1_1") (pintype "passive"))
      (node (ref "R103") (pin "2") (pinfunction "2_2") (pintype "passive"))
    )
    (net (code "151") (name "Net-(Q20-PadC)") (class "Default")
      (node (ref "Q20") (pin "C") (pinfunction "C_C") (pintype "passive"))
      (node (ref "R108") (pin "2") (pinfunction "2_2") (pintype "passive"))
    )
    (net (code "152") (name "Net-(Q21-PadB)") (class "Default")
      (node (ref "Q21") (pin "B") (pinfunction "B_B") (pintype "passive"))
      (node (ref "R108") (pin "1") (pinfunction "1_1") (pintype "passive"))
      (node (ref "R111") (pin "2") (pinfunction "2_2") (pintype "passive"))
    )
    (net (code "153") (name "Net-(Q22-PadC)") (class "Default")
      (node (ref "Q22") (pin "C") (pinfunction "C_C") (pintype "passive"))
      (node (ref "R106") (pin "1") (pinfunction "1_1") (pintype "passive"))
    )
    (net (code "154") (name "Net-(Q27-D)") (class "Default")
      (node (ref "Q27") (pin "3") (pinfunction "D_3") (pintype "passive"))
      (node (ref "R118") (pin "1") (pinfunction "1_1") (pintype "passive"))
    )
    (net (code "155") (name "Net-(R27-Pad1)") (class "Default")
      (node (ref "R27") (pin "1") (pinfunction "1_1") (pintype "passive"))
      (node (ref "R32") (pin "2") (pinfunction "2_2") (pintype "passive"))
    )
    (net (code "156") (name "Net-(R61-Pad2)") (class "Default")
      (node (ref "R61") (pin "2") (pinfunction "2_2") (pintype "passive"))
      (node (ref "R67") (pin "2S") (pinfunction "2S_2S") (pintype "passive"))
    )
    (net (code "157") (name "Net-(R67-Pad1S)") (class "Default")
      (node (ref "R67") (pin "1S") (pinfunction "1S_1S") (pintype "passive"))
      (node (ref "R68") (pin "1") (pinfunction "1_1") (pintype "passive"))
    )
    (net (code "158") (name "Net-(R75-Pad2)") (class "Default")
      (node (ref "R75") (pin "2") (pinfunction "2_2") (pintype "passive"))
      (node (ref "R76") (pin "1") (pinfunction "1_1") (pintype "passive"))
    )
    (net (code "159") (name "Net-(R76-Pad2)") (class "Default")
      (node (ref "R76") (pin "2") (pinfunction "2_2") (pintype "passive"))
      (node (ref "X3") (pin "1") (pinfunction "1_1") (pintype "passive"))
    )
    (net (code "160") (name "Net-(R102-Pad2)") (class "Default")
      (node (ref "R102") (pin "2") (pinfunction "2_2") (pintype "passive"))
      (node (ref "ZD4") (pin "A") (pinfunction "A_A") (pintype "passive"))
    )
    (net (code "161") (name "Net-(X4B-1)") (class "Default")
      (node (ref "F2") (pin "2") (pinfunction "2_2") (pintype "passive"))
      (node (ref "X4") (pin "10") (pinfunction "1_10") (pintype "passive"))
      (node (ref "X4") (pin "6") (pinfunction "1_6") (pintype "passive"))
      (node (ref "X4") (pin "7") (pinfunction "1_7") (pintype "passive"))
      (node (ref "X4") (pin "8") (pinfunction "1_8") (pintype "passive"))
      (node (ref "X4") (pin "9") (pinfunction "1_9") (pintype "passive"))
    )
    (net (code "162") (name "OE") (class "Default")
      (node (ref "IC13") (pin "2") (pinfunction "GPB1_2") (pintype "bidirectional"))
      (node (ref "OE") (pin "1") (pinfunction "1_1") (pintype "passive"))
    )
    (net (code "163") (name "OE_GREEN") (class "Default")
      (node (ref "IC13") (pin "7") (pinfunction "GPB6_7") (pintype "bidirectional"))
      (node (ref "LED1") (pin "GREEN") (pinfunction "AG_GREEN") (pintype "passive"))
    )
    (net (code "164") (name "OE_RED") (class "Default")
      (node (ref "IC13") (pin "8") (pinfunction "GPB7_8") (pintype "bidirectional"))
      (node (ref "LED1") (pin "RED") (pinfunction "AR_RED") (pintype "passive"))
    )
    (net (code "165") (name "OE_SYNC") (class "Default")
      (node (ref "IC7") (pin "4") (pinfunction "A2_4") (pintype "input"))
      (node (ref "X2") (pin "6") (pinfunction "1_6") (pintype "passive"))
    )
    (net (code "166") (name "OE_TRIG") (class "Default")
      (node (ref "IC12") (pin "1") (pinfunction "CLK_1") (pintype "input"))
      (node (ref "RN2") (pin "5") (pinfunction "2_5") (pintype "passive"))
    )
    (net (code "167") (name "OUTC+") (class "Default")
      (node (ref "C93") (pin "1") (pinfunction "1_1") (pintype "passive"))
      (node (ref "C94") (pin "+") (pinfunction "+_+") (pintype "passive"))
      (node (ref "C95") (pin "1") (pinfunction "1_1") (pintype "passive"))
      (node (ref "C96") (pin "1") (pinfunction "1_1") (pintype "passive"))
      (node (ref "J2") (pin "1") (pinfunction "1_1") (pintype "passive"))
      (node (ref "J2") (pin "NC1") (pinfunction "1_NC1") (pintype "passive"))
      (node (ref "J2") (pin "NC2") (pinfunction "1_NC2") (pintype "passive"))
      (node (ref "J2") (pin "NC3") (pinfunction "1_NC3") (pintype "passive"))
      (node (ref "J2") (pin "NC4") (pinfunction "1_NC4") (pintype "passive"))
      (node (ref "X4") (pin "1") (pinfunction "1_1") (pintype "passive"))
      (node (ref "X4") (pin "2") (pinfunction "1_2") (pintype "passive"))
      (node (ref "X4") (pin "3") (pinfunction "1_3") (pintype "passive"))
      (node (ref "X4") (pin "4") (pinfunction "1_4") (pintype "passive"))
      (node (ref "X4") (pin "5") (pinfunction "1_5") (pintype "passive"))
    )
    (net (code "168") (name "OUTC-") (class "Default")
      (node (ref "C94") (pin "-") (pinfunction "-_-") (pintype "passive"))
      (node (ref "C95") (pin "2") (pinfunction "2_2") (pintype "passive"))
      (node (ref "C96") (pin "2") (pinfunction "2_2") (pintype "passive"))
      (node (ref "C97") (pin "2") (pinfunction "2_2") (pintype "passive"))
      (node (ref "J3") (pin "1") (pinfunction "1_1") (pintype "passive"))
      (node (ref "J3") (pin "NC1") (pinfunction "1_NC1") (pintype "passive"))
      (node (ref "J3") (pin "NC2") (pinfunction "1_NC2") (pintype "passive"))
      (node (ref "J3") (pin "NC3") (pinfunction "1_NC3") (pintype "passive"))
      (node (ref "J3") (pin "NC4") (pinfunction "1_NC4") (pintype "passive"))
      (node (ref "X4") (pin "16") (pinfunction "1_16") (pintype "passive"))
      (node (ref "X4") (pin "17") (pinfunction "1_17") (pintype "passive"))
      (node (ref "X4") (pin "18") (pinfunction "1_18") (pintype "passive"))
      (node (ref "X4") (pin "19") (pinfunction "1_19") (pintype "passive"))
      (node (ref "X4") (pin "20") (pinfunction "1_20") (pintype "passive"))
    )
    (net (code "169") (name "OVP_EN") (class "Default")
      (node (ref "IC13") (pin "5") (pinfunction "GPB4_5") (pintype "bidirectional"))
      (node (ref "IC20") (pin "6") (pinfunction "~{SHDN}_6") (pintype "input"))
      (node (ref "R87") (pin "2") (pinfunction "2_2") (pintype "passive"))
    )
    (net (code "170") (name "PE") (class "Default")
      (node (ref "C3") (pin "2") (pinfunction "2_2") (pintype "passive"))
      (node (ref "C4") (pin "1") (pinfunction "1_1") (pintype "passive"))
      (node (ref "C93") (pin "2") (pinfunction "2_2") (pintype "passive"))
      (node (ref "C97") (pin "1") (pinfunction "1_1") (pintype "passive"))
      (node (ref "J1") (pin "1") (pinfunction "P$1_1") (pintype "bidirectional"))
      (node (ref "J1") (pin "2") (pinfunction "P$1_2") (pintype "bidirectional"))
      (node (ref "X3") (pin "3") (pinfunction "1_3") (pintype "passive"))
    )
    (net (code "171") (name "POST_OE") (class "Default")
      (node (ref "IC12") (pin "5") (pinfunction "Q_5") (pintype "output"))
      (node (ref "R54") (pin "2") (pinfunction "2_2") (pintype "passive"))
    )
    (net (code "172") (name "POST_OUT+") (class "Default")
      (node (ref "C47") (pin "1") (pinfunction "1_1") (pintype "passive"))
      (node (ref "C61") (pin "1") (pinfunction "1_1") (pintype "passive"))
      (node (ref "D8") (pin "A") (pinfunction "A_A") (pintype "passive"))
      (node (ref "F1") (pin "1") (pinfunction "1_1") (pintype "passive"))
      (node (ref "Q3") (pin "2") (pinfunction "C_2") (pintype "passive"))
      (node (ref "Q4") (pin "2") (pinfunction "C_2") (pintype "passive"))
      (node (ref "R10") (pin "2") (pinfunction "2_2") (pintype "passive"))
      (node (ref "R27") (pin "2") (pinfunction "2_2") (pintype "passive"))
      (node (ref "R28") (pin "2") (pinfunction "2_2") (pintype "passive"))
      (node (ref "R29") (pin "2") (pinfunction "2_2") (pintype "passive"))
      (node (ref "R30") (pin "1") (pinfunction "1_1") (pintype "passive"))
      (node (ref "ZD2") (pin "C") (pinfunction "C_C") (pintype "passive"))
    )
    (net (code "173") (name "POST_OUT-") (class "Default")
      (node (ref "C41") (pin "1") (pinfunction "1_1") (pintype "passive"))
      (node (ref "C92") (pin "-") (pinfunction "-_-") (pintype "passive"))
      (node (ref "C98") (pin "2") (pinfunction "2_2") (pintype "passive"))
      (node (ref "D14") (pin "A") (pinfunction "A_A") (pintype "passive"))
      (node (ref "JP4") (pin "1") (pinfunction "1_1") (pintype "passive"))
      (node (ref "K1") (pin "7") (pinfunction "O_7") (pintype "passive"))
      (node (ref "Q10") (pin "MB") (pinfunction "D_MB") (pintype "passive"))
      (node (ref "Q11") (pin "MB") (pinfunction "D_MB") (pintype "passive"))
      (node (ref "Q22") (pin "E") (pinfunction "E_E") (pintype "passive"))
      (node (ref "R109") (pin "1") (pinfunction "1_1") (pintype "passive"))
      (node (ref "R112") (pin "1") (pinfunction "1_1") (pintype "passive"))
      (node (ref "X4") (pin "11") (pinfunction "1_11") (pintype "passive"))
      (node (ref "X4") (pin "12") (pinfunction "1_12") (pintype "passive"))
      (node (ref "X4") (pin "13") (pinfunction "1_13") (pintype "passive"))
      (node (ref "X4") (pin "14") (pinfunction "1_14") (pintype "passive"))
      (node (ref "X4") (pin "15") (pinfunction "1_15") (pintype "passive"))
      (node (ref "ZD5") (pin "A") (pinfunction "A_A") (pintype "passive"))
    )
    (net (code "174") (name "POST_OUTF+") (class "Default")
      (node (ref "C90") (pin "1") (pinfunction "1_1") (pintype "passive"))
      (node (ref "C91") (pin "1") (pinfunction "1_1") (pintype "passive"))
      (node (ref "C92") (pin "+") (pinfunction "+_+") (pintype "passive"))
      (node (ref "F1") (pin "2") (pinfunction "2_2") (pintype "passive"))
      (node (ref "F2") (pin "1") (pinfunction "1_1") (pintype "passive"))
      (node (ref "JP3") (pin "2") (pinfunction "2_2") (pintype "passive"))
      (node (ref "K1") (pin "2") (pinfunction "O_2") (pintype "passive"))
      (node (ref "Q13") (pin "A1") (pinfunction "A1_A1") (pintype "passive"))
      (node (ref "Q18") (pin "MB") (pinfunction "D_MB") (pintype "passive"))
      (node (ref "Q20") (pin "E") (pinfunction "E_E") (pintype "passive"))
      (node (ref "R104") (pin "2") (pinfunction "2_2") (pintype "passive"))
      (node (ref "R85") (pin "2") (pinfunction "2_2") (pintype "passive"))
      (node (ref "ZD4") (pin "C") (pinfunction "C_C") (pintype "passive"))
      (node (ref "ZD5") (pin "C") (pinfunction "C_C") (pintype "passive"))
    )
    (net (code "175") (name "PREG_IN-") (class "Default")
      (node (ref "C10") (pin "2") (pinfunction "2_2") (pintype "passive"))
      (node (ref "C11") (pin "-") (pinfunction "-_-") (pintype "passive"))
      (node (ref "C15") (pin "2") (pinfunction "2_2") (pintype "passive"))
      (node (ref "C16") (pin "-") (pinfunction "-_-") (pintype "passive"))
      (node (ref "C2") (pin "-") (pinfunction "-_-") (pintype "passive"))
      (node (ref "C3") (pin "1") (pinfunction "1_1") (pintype "passive"))
      (node (ref "C5") (pin "2") (pinfunction "2_2") (pintype "passive"))
      (node (ref "C6") (pin "2") (pinfunction "2_2") (pintype "passive"))
      (node (ref "C7") (pin "2") (pinfunction "2_2") (pintype "passive"))
      (node (ref "D2") (pin "1") (pinfunction "A_1") (pintype "passive"))
      (node (ref "D2") (pin "2") (pinfunction "A_2") (pintype "passive"))
      (node (ref "IC1") (pin "TP") (pinfunction "PGND_TP") (pintype "passive"))
      (node (ref "L1") (pin "4") (pinfunction "2_4") (pintype "passive"))
      (node (ref "R2") (pin "1") (pinfunction "1_1") (pintype "passive"))
      (node (ref "R5") (pin "1") (pinfunction "1_1") (pintype "passive"))
      (node (ref "SH1") (pin "1") (pinfunction "GND_A_1") (pintype "bidirectional"))
      (node (ref "SH2") (pin "2") (pinfunction "GND_B_2") (pintype "bidirectional"))
      (node (ref "SH3") (pin "2") (pinfunction "GND_B_2") (pintype "bidirectional"))
      (node (ref "ZD1") (pin "A") (pinfunction "A_A") (pintype "passive"))
    )
    (net (code "176") (name "PREG_OUT+") (class "Default")
      (node (ref "C13") (pin "+") (pinfunction "+_+") (pintype "passive"))
      (node (ref "C14") (pin "1") (pinfunction "1_1") (pintype "passive"))
      (node (ref "D8") (pin "C") (pinfunction "C_C") (pintype "passive"))
      (node (ref "L3") (pin "2") (pinfunction "2_2") (pintype "passive"))
      (node (ref "R25") (pin "1") (pinfunction "1_1") (pintype "passive"))
      (node (ref "R26") (pin "1") (pinfunction "1_1") (pintype "passive"))
      (node (ref "R33") (pin "2") (pinfunction "2_2") (pintype "passive"))
      (node (ref "R4") (pin "2") (pinfunction "2_2") (pintype "passive"))
    )
    (net (code "177") (name "PREG_OUT-") (class "Default")
      (node (ref "C13") (pin "-") (pinfunction "-_-") (pintype "passive"))
      (node (ref "C14") (pin "2") (pinfunction "2_2") (pintype "passive"))
      (node (ref "D14") (pin "C") (pinfunction "C_C") (pintype "passive"))
      (node (ref "Q18") (pin "1") (pinfunction "S_1") (pintype "passive"))
      (node (ref "Q18") (pin "2") (pinfunction "S_2") (pintype "passive"))
      (node (ref "Q18") (pin "3") (pinfunction "S_3") (pintype "passive"))
      (node (ref "Q19") (pin "E") (pinfunction "E_E") (pintype "passive"))
      (node (ref "Q5") (pin "2") (pinfunction "D_2") (pintype "passive"))
      (node (ref "R103") (pin "1") (pinfunction "1_1") (pintype "passive"))
      (node (ref "R32") (pin "1") (pinfunction "1_1") (pintype "passive"))
      (node (ref "R67") (pin "1") (pinfunction "1_1") (pintype "passive"))
      (node (ref "R93") (pin "1") (pinfunction "1_1") (pintype "passive"))
      (node (ref "SH2") (pin "1") (pinfunction "GND_A_1") (pintype "bidirectional"))
    )
    (net (code "178") (name "PRE_OE") (class "Default")
      (node (ref "D1") (pin "A") (pinfunction "A_A") (pintype "passive"))
      (node (ref "IC12") (pin "2") (pinfunction "D_2") (pintype "input"))
      (node (ref "OE") (pin "2") (pinfunction "2_2") (pintype "passive"))
    )
    (net (code "179") (name "PWRGOOD") (class "Default")
      (node (ref "D16") (pin "C") (pinfunction "C_C") (pintype "passive"))
      (node (ref "IC13") (pin "24") (pinfunction "GPA3_24") (pintype "bidirectional"))
      (node (ref "IC2") (pin "6") (pinfunction "PWRGD_6") (pintype "output"))
      (node (ref "R17") (pin "2") (pinfunction "2_2") (pintype "passive"))
    )
    (net (code "180") (name "RSENSE") (class "Default")
      (node (ref "IC13") (pin "3") (pinfunction "GPB2_3") (pintype "bidirectional"))
      (node (ref "Q23") (pin "1") (pinfunction "G_1") (pintype "passive"))
      (node (ref "R114") (pin "2") (pinfunction "2_2") (pintype "passive"))
    )
    (net (code "181") (name "SCLK") (class "Default")
      (node (ref "IC13") (pin "12") (pinfunction "SCK_12") (pintype "input"))
      (node (ref "IC15") (pin "3") (pinfunction "SCLK_3") (pintype "input"))
      (node (ref "IC16") (pin "6") (pinfunction "SCLK_6") (pintype "input"))
      (node (ref "IC18") (pin "1") (pinfunction "SCLK_1") (pintype "input"))
      (node (ref "RN2") (pin "8") (pinfunction "2_8") (pintype "passive"))
    )
    (net (code "182") (name "SENSE+") (class "Default")
      (node (ref "JP3") (pin "1") (pinfunction "1_1") (pintype "passive"))
      (node (ref "K1") (pin "3") (pinfunction "P_3") (pintype "passive"))
      (node (ref "R105") (pin "1") (pinfunction "1_1") (pintype "passive"))
      (node (ref "R45") (pin "2") (pinfunction "2_2") (pintype "passive"))
    )
    (net (code "183") (name "SENSE-") (class "Default")
      (node (ref "JP4") (pin "2") (pinfunction "2_2") (pintype "passive"))
      (node (ref "K1") (pin "6") (pinfunction "P_6") (pintype "passive"))
      (node (ref "R110") (pin "2") (pinfunction "2_2") (pintype "passive"))
      (node (ref "R46") (pin "2") (pinfunction "2_2") (pintype "passive"))
    )
    (net (code "184") (name "SENSE_ERR") (class "Default")
      (node (ref "IC13") (pin "21") (pinfunction "GPA0_21") (pintype "bidirectional"))
      (node (ref "Q21") (pin "C") (pinfunction "C_C") (pintype "passive"))
      (node (ref "R107") (pin "1") (pinfunction "1_1") (pintype "passive"))
    )
    (net (code "185") (name "SGND") (class "Default")
      (node (ref "C17") (pin "2") (pinfunction "2_2") (pintype "passive"))
      (node (ref "C18") (pin "2") (pinfunction "2_2") (pintype "passive"))
      (node (ref "C9") (pin "1") (pinfunction "1_1") (pintype "passive"))
      (node (ref "IC1") (pin "1") (pinfunction "PLLIN/MODE_1") (pintype "input"))
      (node (ref "IC1") (pin "2") (pinfunction "FREQ_2") (pintype "input"))
      (node (ref "IC1") (pin "3") (pinfunction "SGND_3") (pintype "passive"))
      (node (ref "R11") (pin "2") (pinfunction "2_2") (pintype "passive"))
      (node (ref "SH3") (pin "1") (pinfunction "GND_A_1") (pintype "bidirectional"))
    )
    (net (code "186") (name "TEMP_CS") (class "Default")
      (node (ref "IC15") (pin "1") (pinfunction "~{CS}_1") (pintype "input"))
      (node (ref "RN1") (pin "5") (pinfunction "2_5") (pintype "passive"))
    )
    (net (code "187") (name "U_MON") (class "Default")
      (node (ref "C43") (pin "2") (pinfunction "2_2") (pintype "passive"))
      (node (ref "IC9") (pin "7") (pinfunction "OUT_7") (pintype "output"))
      (node (ref "R50") (pin "1") (pinfunction "1_1") (pintype "passive"))
      (node (ref "R52") (pin "1") (pinfunction "1_1") (pintype "passive"))
      (node (ref "R80") (pin "1") (pinfunction "1_1") (pintype "passive"))
      (node (ref "R83") (pin "1") (pinfunction "1_1") (pintype "passive"))
    )
    (net (code "188") (name "U_SERVO") (class "Default")
      (node (ref "C44") (pin "2") (pinfunction "2_2") (pintype "passive"))
      (node (ref "C46") (pin "2") (pinfunction "2_2") (pintype "passive"))
      (node (ref "D12") (pin "C") (pinfunction "C_C") (pintype "passive"))
      (node (ref "IC9") (pin "1") (pinfunction "OUT_1") (pintype "output"))
      (node (ref "R42") (pin "1") (pinfunction "1_1") (pintype "passive"))
      (node (ref "R86") (pin "1") (pinfunction "1_1") (pintype "passive"))
    )
    (net (code "189") (name "U_SET") (class "Default")
      (node (ref "IC17") (pin "3") (pinfunction "NC_3") (pintype "bidirectional"))
      (node (ref "JP2") (pin "1") (pinfunction "1_1") (pintype "passive"))
      (node (ref "R78") (pin "1") (pinfunction "1_1") (pintype "passive"))
      (node (ref "U_SET") (pin "2") (pinfunction "2_2") (pintype "passive"))
    )
    (net (code "190") (name "U_SET_OUT") (class "Default")
      (node (ref "IC17") (pin "4") (pinfunction "COM_4") (pintype "bidirectional"))
      (node (ref "JP2") (pin "2") (pinfunction "2_2") (pintype "passive"))
      (node (ref "R48") (pin "1") (pinfunction "1_1") (pintype "passive"))
      (node (ref "R95") (pin "1") (pinfunction "1_1") (pintype "passive"))
    )
    (net (code "191") (name "V+") (class "Default")
      (node (ref "C49") (pin "2") (pinfunction "2_2") (pintype "passive"))
      (node (ref "C50") (pin "1") (pinfunction "1_1") (pintype "passive"))
      (node (ref "C51") (pin "2") (pinfunction "2_2") (pintype "passive"))
      (node (ref "C52") (pin "2") (pinfunction "2_2") (pintype "passive"))
      (node (ref "C53") (pin "2") (pinfunction "2_2") (pintype "passive"))
      (node (ref "C62") (pin "1") (pinfunction "1_1") (pintype "passive"))
      (node (ref "C67") (pin "1") (pinfunction "1_1") (pintype "passive"))
      (node (ref "C70") (pin "1") (pinfunction "1_1") (pintype "passive"))
      (node (ref "C72") (pin "2") (pinfunction "2_2") (pintype "passive"))
      (node (ref "C74") (pin "1") (pinfunction "1_1") (pintype "passive"))
      (node (ref "C84") (pin "1") (pinfunction "1_1") (pintype "passive"))
      (node (ref "C85") (pin "2") (pinfunction "2_2") (pintype "passive"))
      (node (ref "C88") (pin "2") (pinfunction "2_2") (pintype "passive"))
      (node (ref "FB1") (pin "P$2") (pinfunction "2_P$2") (pintype "passive"))
      (node (ref "IC10") (pin "8") (pinfunction "V+_8") (pintype "power_in"))
      (node (ref "IC11") (pin "7") (pinfunction "V+_7") (pintype "power_in"))
      (node (ref "IC14") (pin "2") (pinfunction "VIN_2") (pintype "passive"))
      (node (ref "IC16") (pin "1") (pinfunction "VDD_1") (pintype "power_in"))
      (node (ref "IC17") (pin "5") (pinfunction "VDD_5") (pintype "power_in"))
      (node (ref "IC19") (pin "8") (pinfunction "V+_8") (pintype "power_in"))
      (node (ref "IC20") (pin "1") (pinfunction "+VCC_1") (pintype "passive"))
      (node (ref "IC20") (pin "5") (pinfunction "~{LE}_5") (pintype "input"))
      (node (ref "IC21") (pin "5") (pinfunction "VDD_5") (pintype "power_in"))
      (node (ref "IC9") (pin "8") (pinfunction "V+_8") (pintype "power_in"))
      (node (ref "R40") (pin "2") (pinfunction "2_2") (pintype "passive"))
      (node (ref "R82") (pin "1") (pinfunction "1_1") (pintype "passive"))
    )
    (net (code "192") (name "V-") (class "Default")
      (node (ref "C54") (pin "2") (pinfunction "2_2") (pintype "passive"))
      (node (ref "C56") (pin "2") (pinfunction "2_2") (pintype "passive"))
      (node (ref "C57") (pin "1") (pinfunction "1_1") (pintype "passive"))
      (node (ref "C58") (pin "2") (pinfunction "2_2") (pintype "passive"))
      (node (ref "C59") (pin "2") (pinfunction "2_2") (pintype "passive"))
      (node (ref "C89") (pin "2") (pinfunction "2_2") (pintype "passive"))
      (node (ref "FB3") (pin "P$2") (pinfunction "2_P$2") (pintype "passive"))
      (node (ref "IC10") (pin "4") (pinfunction "V-_4") (pintype "power_in"))
      (node (ref "IC11") (pin "4") (pinfunction "V-_4") (pintype "power_in"))
      (node (ref "IC19") (pin "4") (pinfunction "V-_4") (pintype "power_in"))
      (node (ref "IC9") (pin "4") (pinfunction "V-_4") (pintype "power_in"))
    )
    (net (code "193") (name "unconnected-(IC1-PGOOD-Pad7)") (class "Default")
      (node (ref "IC1") (pin "7") (pinfunction "PGOOD_7") (pintype "output"))
    )
    (net (code "194") (name "unconnected-(IC12A-~{Q}-Pad3)") (class "Default")
      (node (ref "IC12") (pin "3") (pinfunction "~{Q}_3") (pintype "output"))
    )
    (net (code "195") (name "unconnected-(IC13-GPB5-Pad6)") (class "Default")
      (node (ref "IC13") (pin "6") (pinfunction "GPB5_6") (pintype "bidirectional"))
    )
    (net (code "196") (name "unconnected-(IC13-INTB-Pad19)") (class "Default")
      (node (ref "IC13") (pin "19") (pinfunction "INTB_19") (pintype "output"))
    )
    (net (code "197") (name "unconnected-(IC14-TEMP-Pad3)") (class "Default")
      (node (ref "IC14") (pin "3") (pinfunction "TEMP_3") (pintype "input"))
    )
    (net (code "198") (name "unconnected-(IC21-NC-Pad3)") (class "Default")
      (node (ref "IC21") (pin "3") (pinfunction "NC_3") (pintype "bidirectional"))
    )
    (net (code "199") (name "~{ADC_DRDY}") (class "Default")
      (node (ref "IC13") (pin "25") (pinfunction "GPA4_25") (pintype "bidirectional"))
      (node (ref "IC18") (pin "14") (pinfunction "~{DRDY}_14") (pintype "output"))
    )
    (net (code "200") (name "~{DP_DRIVE}") (class "Default")
      (node (ref "D9") (pin "A") (pinfunction "A_A") (pintype "passive"))
      (node (ref "Q7") (pin "E") (pinfunction "E_E") (pintype "passive"))
      (node (ref "R74") (pin "1") (pinfunction "1_1") (pintype "passive"))
    )
    (net (code "201") (name "~{OVP_FAULT}") (class "Default")
      (node (ref "C64") (pin "1") (pinfunction "1_1") (pintype "passive"))
      (node (ref "D15") (pin "C") (pinfunction "C_C") (pintype "passive"))
      (node (ref "IC13") (pin "26") (pinfunction "GPA5_26") (pintype "bidirectional"))
      (node (ref "Q17") (pin "3") (pinfunction "D_3") (pintype "passive"))
      (node (ref "R70") (pin "2") (pinfunction "2_2") (pintype "passive"))
    )
    (net (code "202") (name "~{RESET}") (class "Default")
      (node (ref "IC7") (pin "12") (pinfunction "B3_12") (pintype "output"))
      (node (ref "JP1") (pin "1") (pinfunction "1_1") (pintype "passive"))
    )
    (net (code "203") (name "~{SET_DP}") (class "Default")
      (node (ref "IC13") (pin "1") (pinfunction "GPB0_1") (pintype "bidirectional"))
      (node (ref "Q12") (pin "1") (pinfunction "G_1") (pintype "passive"))
      (node (ref "R72") (pin "2") (pinfunction "2_2") (pintype "passive"))
    )
  )
)
